# mcu_stm32h5.net
KiCad netlist of a schematic drawn in Altium Designer
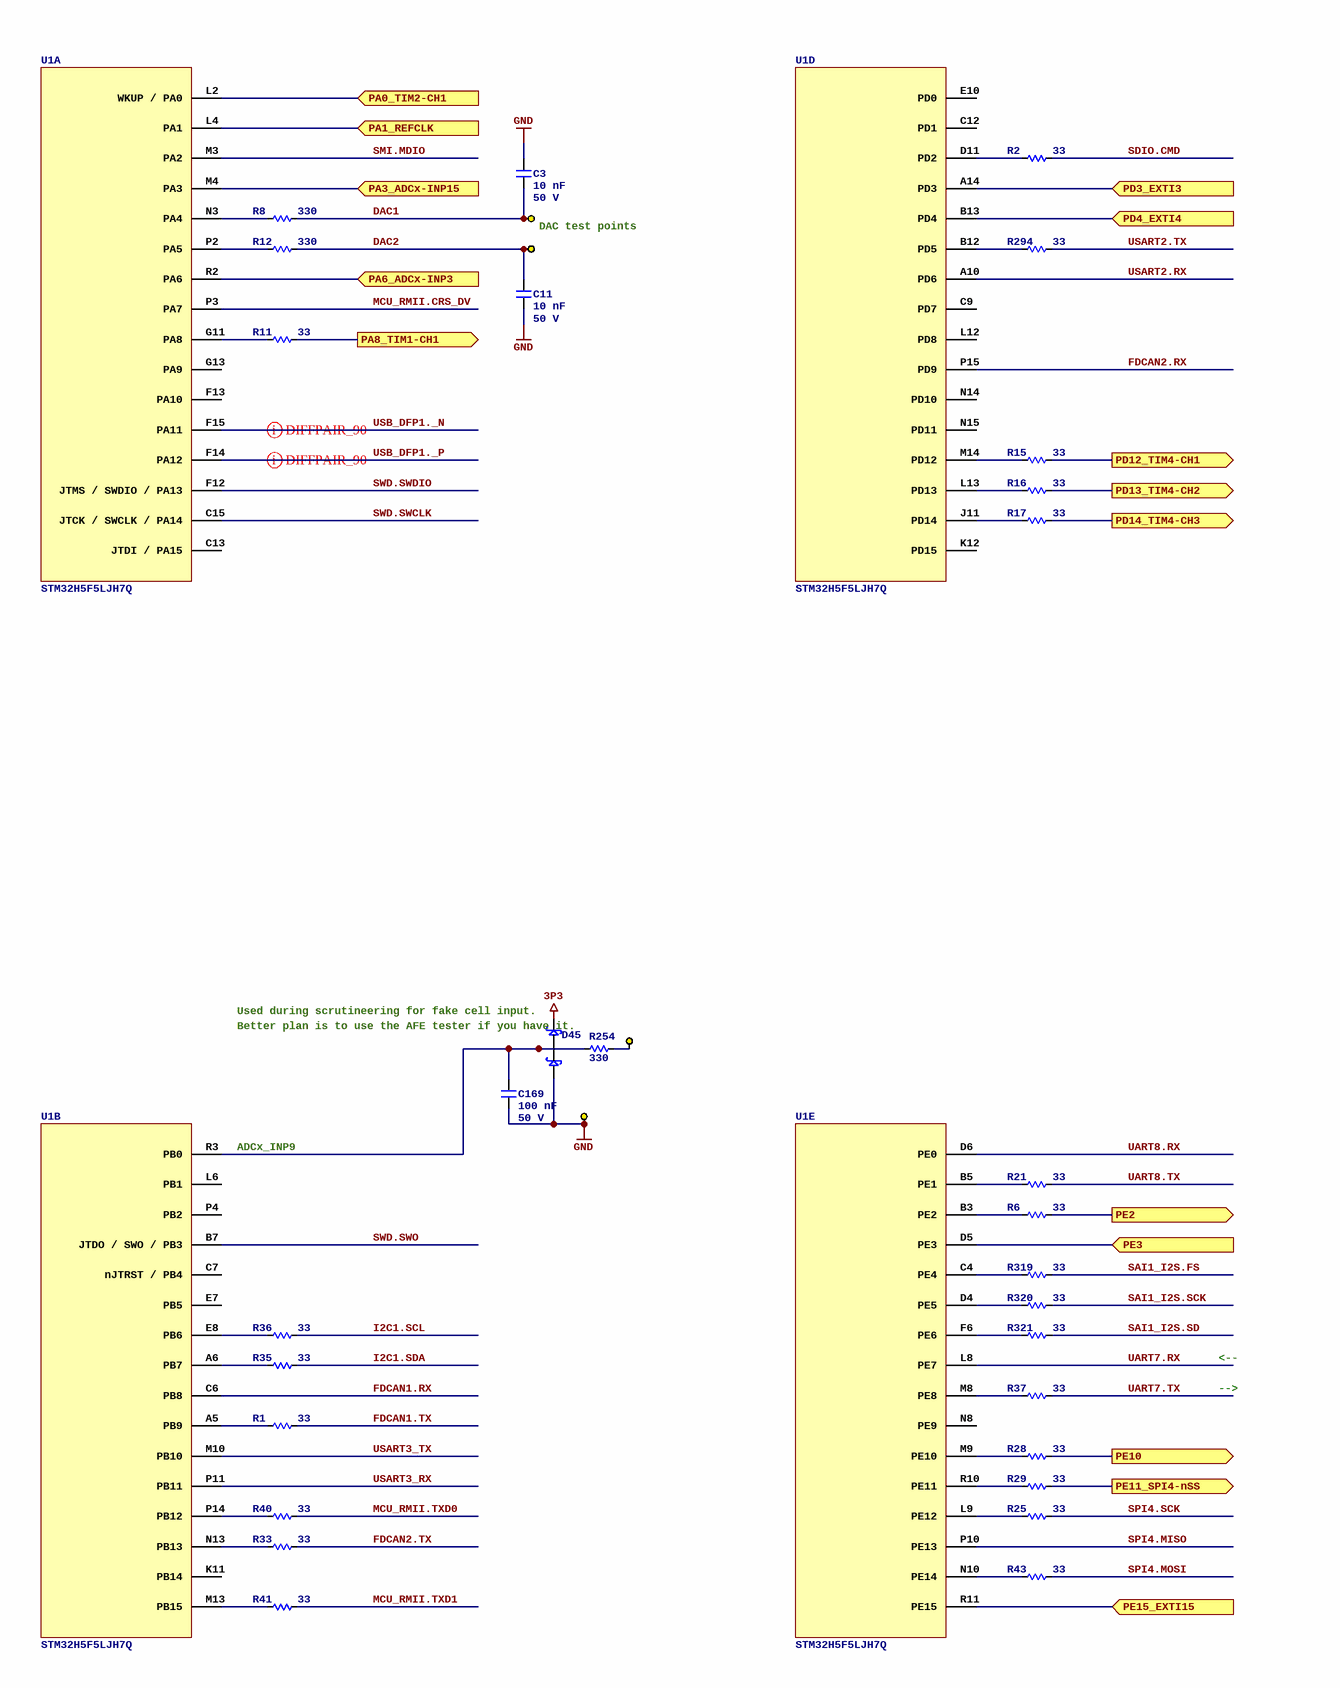
[diagram p0: mcu_stm32h5.SchDoc, top left]
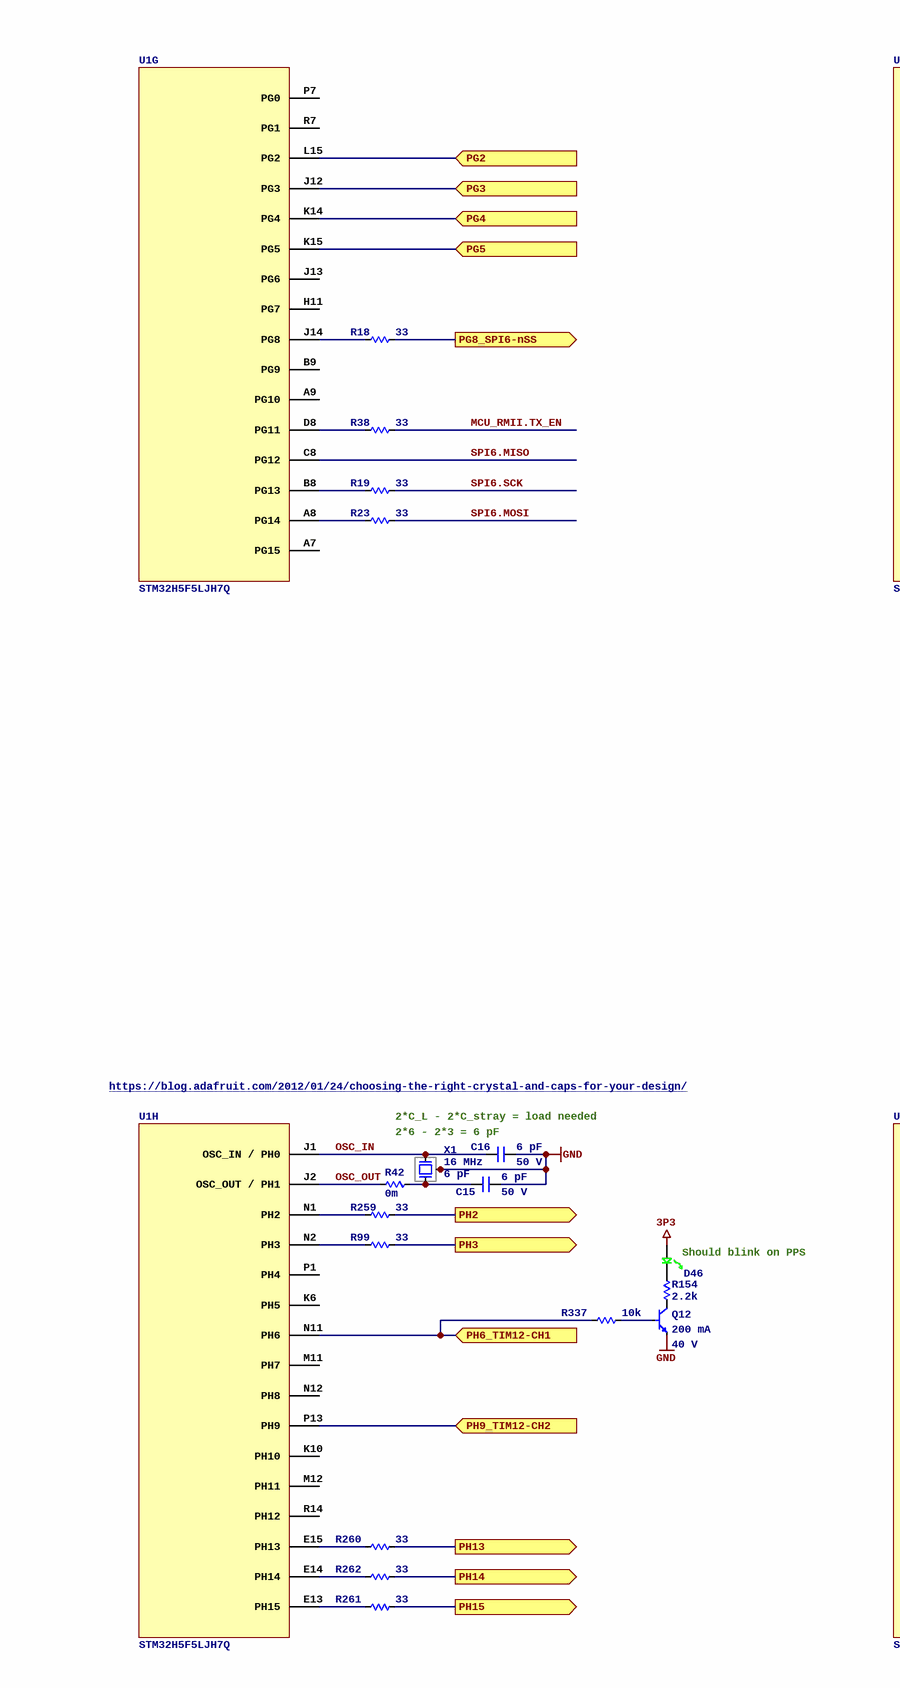
[diagram p1: mcu_stm32h5.SchDoc, top middle]
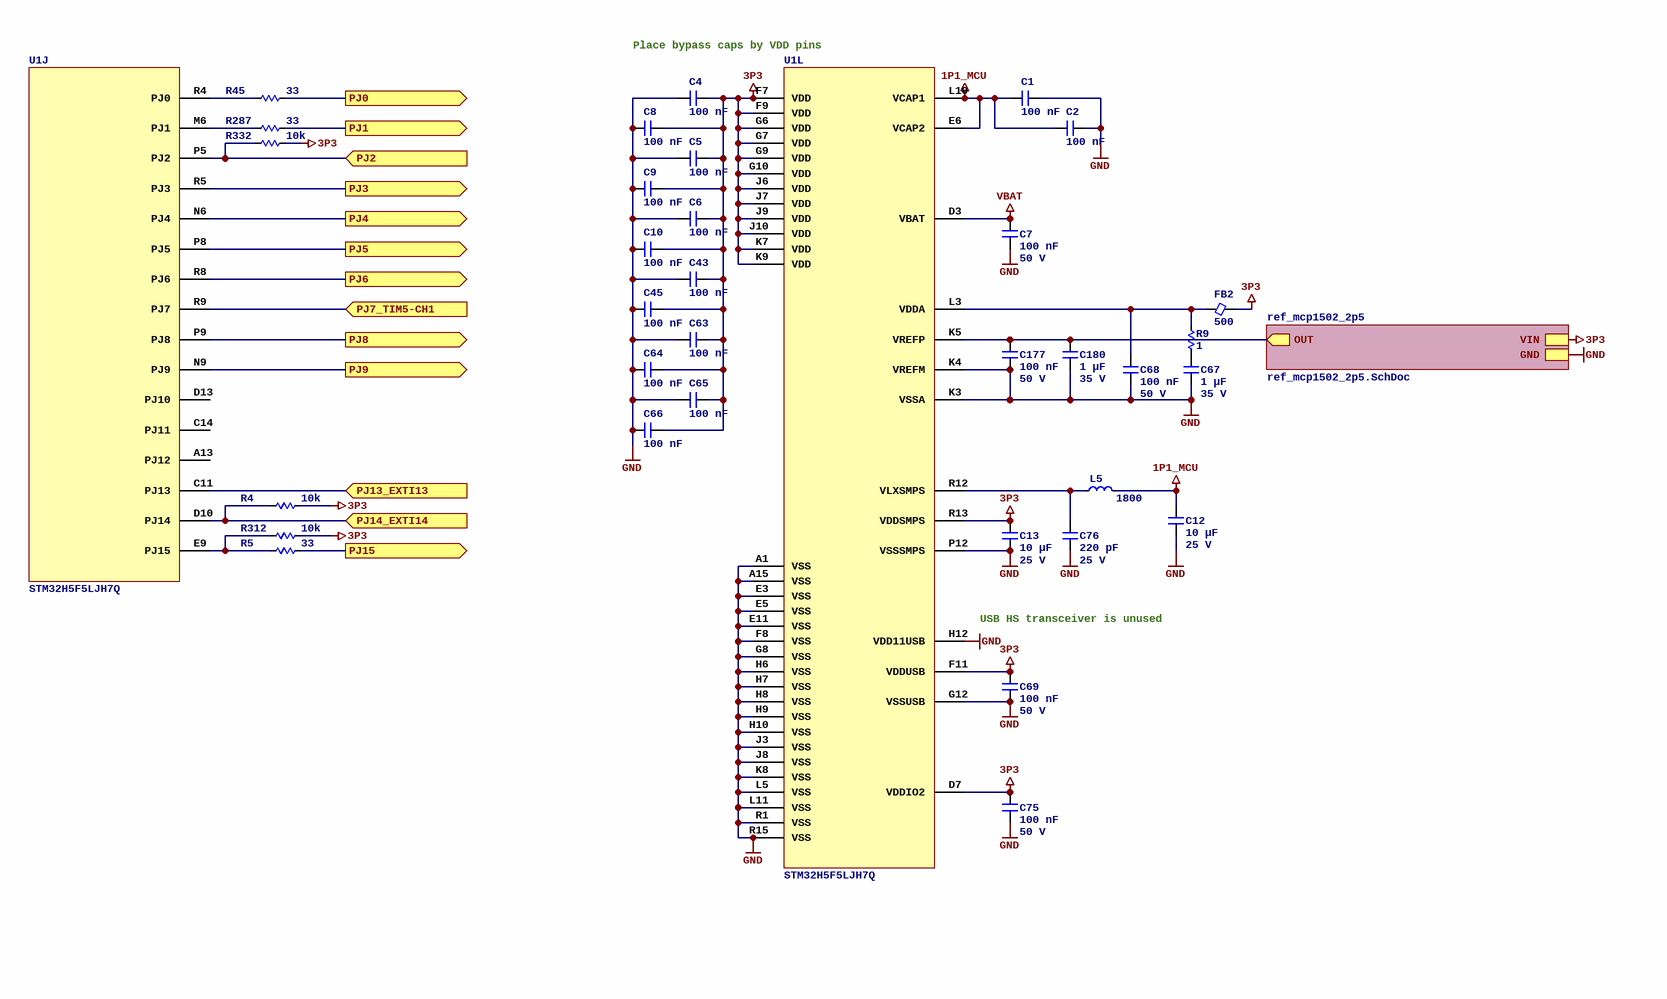
[diagram p2: mcu_stm32h5.SchDoc, top right]
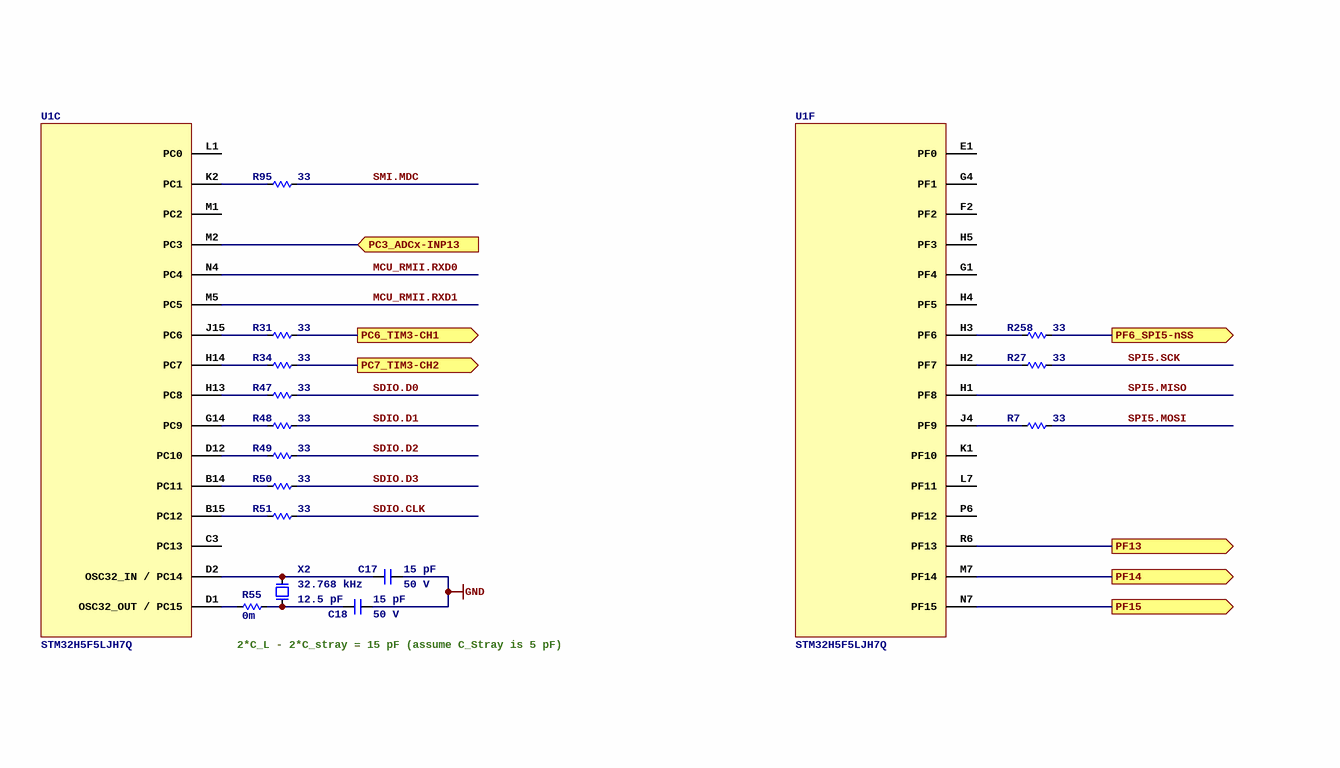
[diagram p3: mcu_stm32h5.SchDoc, bottom left]
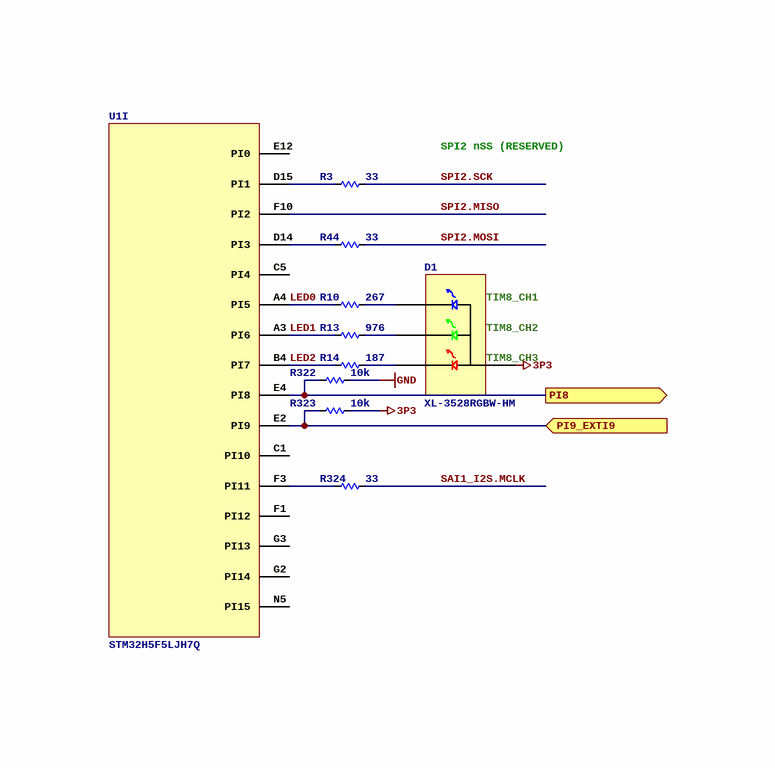
[diagram p4: mcu_stm32h5.SchDoc, bottom middle]
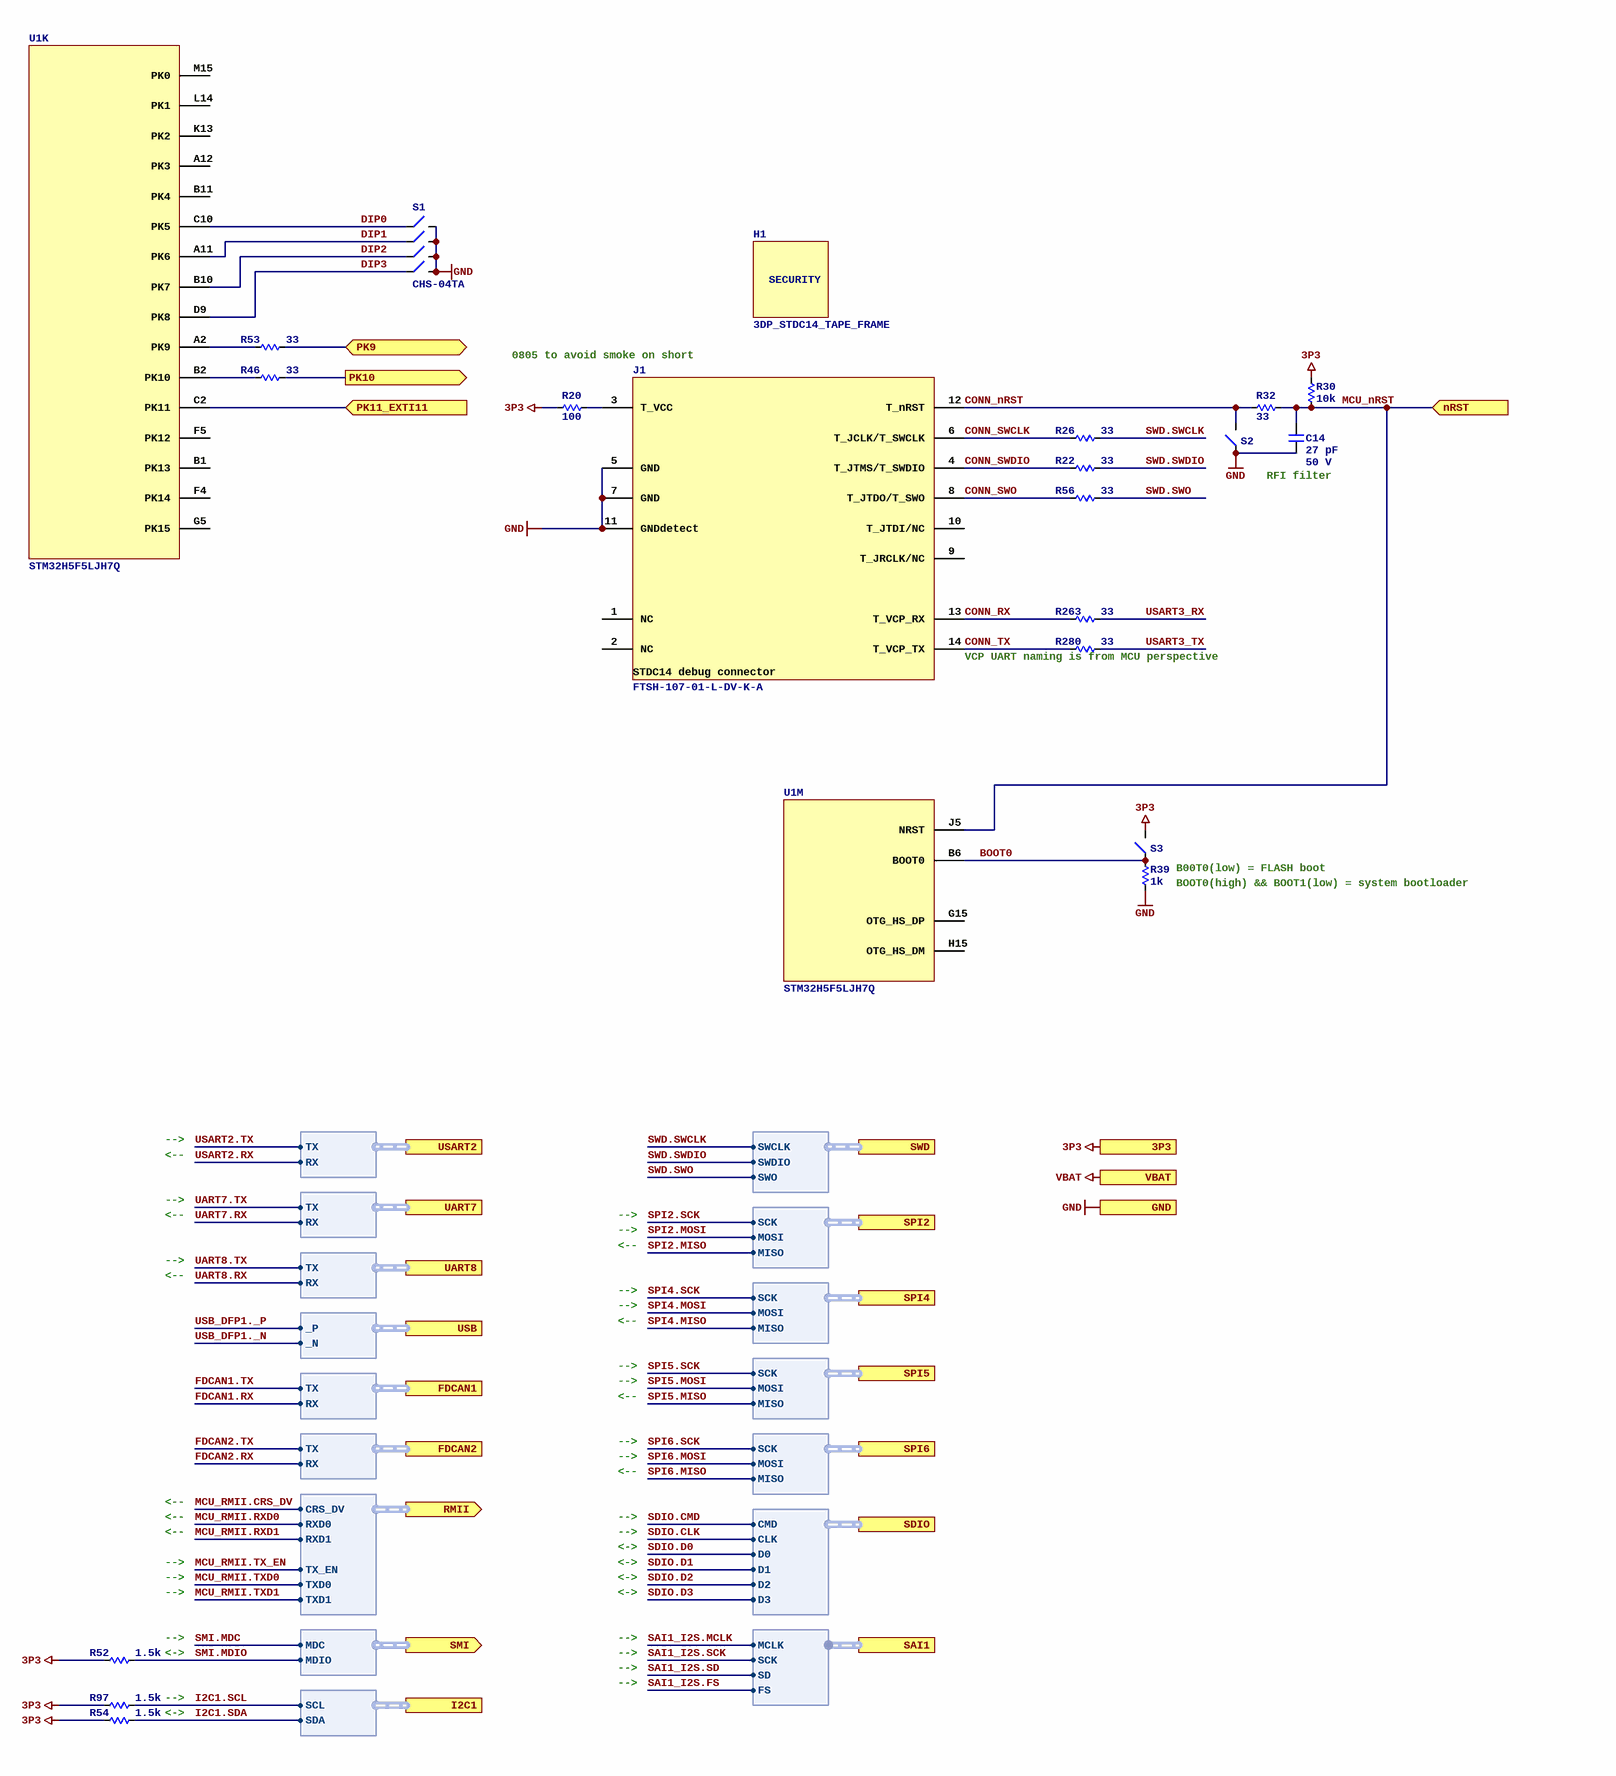
[diagram p5: mcu_stm32h5.SchDoc, bottom right]

(export (version "E")
  (design (tool "Eeschema 10.0.6"))
  (components
    (comp (ref "C1")
      (value "CL05B104KB54PNC")
      (footprint "C0402")
      (fields (field (name "CAPACITANCE") "100 nF") (field (name "MANUFACTURER") "Samsung Electro-Mechanics"))
      (libsource (lib "database") (part "__template_cap"))
    )
    (comp (ref "C2")
      (value "CL05B104KB54PNC")
      (footprint "C0402")
      (fields (field (name "CAPACITANCE") "100 nF") (field (name "MANUFACTURER") "Samsung Electro-Mechanics"))
      (libsource (lib "database") (part "__template_cap"))
    )
    (comp (ref "C3")
      (value "CL05B103KB5NNNC")
      (footprint "C0402")
      (fields
        (field (name "CAPACITANCE") "10 nF")
        (field (name "MANUFACTURER") "Samsung Electro-Mechanics")
        (field (name "VOLTAGE RATING") "50 V")
      )
      (libsource (lib "database") (part "__template_cap"))
    )
    (comp (ref "C4")
      (value "CL05B104KB54PNC")
      (footprint "C0402")
      (fields (field (name "CAPACITANCE") "100 nF") (field (name "MANUFACTURER") "Samsung Electro-Mechanics"))
      (libsource (lib "database") (part "__template_cap"))
    )
    (comp (ref "C5")
      (value "CL05B104KB54PNC")
      (footprint "C0402")
      (fields (field (name "CAPACITANCE") "100 nF") (field (name "MANUFACTURER") "Samsung Electro-Mechanics"))
      (libsource (lib "database") (part "__template_cap"))
    )
    (comp (ref "C6")
      (value "CL05B104KB54PNC")
      (footprint "C0402")
      (fields (field (name "CAPACITANCE") "100 nF") (field (name "MANUFACTURER") "Samsung Electro-Mechanics"))
      (libsource (lib "database") (part "__template_cap"))
    )
    (comp (ref "C7")
      (value "CL05B104KB54PNC")
      (footprint "C0402")
      (fields
        (field (name "CAPACITANCE") "100 nF")
        (field (name "MANUFACTURER") "Samsung Electro-Mechanics")
        (field (name "VOLTAGE RATING") "50 V")
      )
      (libsource (lib "database") (part "__template_cap"))
    )
    (comp (ref "C8")
      (value "CL05B104KB54PNC")
      (footprint "C0402")
      (fields (field (name "CAPACITANCE") "100 nF") (field (name "MANUFACTURER") "Samsung Electro-Mechanics"))
      (libsource (lib "database") (part "__template_cap"))
    )
    (comp (ref "C9")
      (value "CL05B104KB54PNC")
      (footprint "C0402")
      (fields (field (name "CAPACITANCE") "100 nF") (field (name "MANUFACTURER") "Samsung Electro-Mechanics"))
      (libsource (lib "database") (part "__template_cap"))
    )
    (comp (ref "C10")
      (value "CL05B104KB54PNC")
      (footprint "C0402")
      (fields (field (name "CAPACITANCE") "100 nF") (field (name "MANUFACTURER") "Samsung Electro-Mechanics"))
      (libsource (lib "database") (part "__template_cap"))
    )
    (comp (ref "C11")
      (value "CL05B103KB5NNNC")
      (footprint "C0402")
      (fields
        (field (name "CAPACITANCE") "10 nF")
        (field (name "MANUFACTURER") "Samsung Electro-Mechanics")
        (field (name "VOLTAGE RATING") "50 V")
      )
      (libsource (lib "database") (part "__template_cap"))
    )
    (comp (ref "C12")
      (value "CL10A106MA8NRNC")
      (footprint "C0603")
      (fields
        (field (name "CAPACITANCE") "10 µF")
        (field (name "MANUFACTURER") "Samsung Electro-Mechanics")
        (field (name "VOLTAGE RATING") "25 V")
      )
      (libsource (lib "database") (part "__template_cap"))
    )
    (comp (ref "C13")
      (value "CL10A106MA8NRNC")
      (footprint "C0603")
      (fields
        (field (name "CAPACITANCE") "10 µF")
        (field (name "MANUFACTURER") "Samsung Electro-Mechanics")
        (field (name "VOLTAGE RATING") "25 V")
      )
      (libsource (lib "database") (part "__template_cap"))
    )
    (comp (ref "C14")
      (value "0402CG270J500NT")
      (footprint "C0402")
      (fields
        (field (name "CAPACITANCE") "27 pF")
        (field (name "MANUFACTURER") "FH(Guangdong Fenghua Advanced Tech)")
        (field (name "VOLTAGE RATING") "50 V")
      )
      (libsource (lib "database") (part "__template_cap"))
    )
    (comp (ref "C15")
      (value "0402CG6R0C500NT")
      (footprint "C0402")
      (fields
        (field (name "CAPACITANCE") "6 pF")
        (field (name "MANUFACTURER") "FH(Guangdong Fenghua Advanced Tech)")
        (field (name "VOLTAGE RATING") "50 V")
      )
      (libsource (lib "database") (part "__template_cap"))
    )
    (comp (ref "C16")
      (value "0402CG6R0C500NT")
      (footprint "C0402")
      (fields
        (field (name "CAPACITANCE") "6 pF")
        (field (name "MANUFACTURER") "FH(Guangdong Fenghua Advanced Tech)")
        (field (name "VOLTAGE RATING") "50 V")
      )
      (libsource (lib "database") (part "__template_cap"))
    )
    (comp (ref "C17")
      (value "0402CG150J500NT")
      (footprint "C0402")
      (fields
        (field (name "CAPACITANCE") "15 pF")
        (field (name "MANUFACTURER") "FH(Guangdong Fenghua Advanced Tech)")
        (field (name "VOLTAGE RATING") "50 V")
      )
      (libsource (lib "database") (part "__template_cap"))
    )
    (comp (ref "C18")
      (value "0402CG150J500NT")
      (footprint "C0402")
      (fields
        (field (name "CAPACITANCE") "15 pF")
        (field (name "MANUFACTURER") "FH(Guangdong Fenghua Advanced Tech)")
        (field (name "VOLTAGE RATING") "50 V")
      )
      (libsource (lib "database") (part "__template_cap"))
    )
    (comp (ref "C43")
      (value "CL05B104KB54PNC")
      (footprint "C0402")
      (fields (field (name "CAPACITANCE") "100 nF") (field (name "MANUFACTURER") "Samsung Electro-Mechanics"))
      (libsource (lib "database") (part "__template_cap"))
    )
    (comp (ref "C45")
      (value "CL05B104KB54PNC")
      (footprint "C0402")
      (fields (field (name "CAPACITANCE") "100 nF") (field (name "MANUFACTURER") "Samsung Electro-Mechanics"))
      (libsource (lib "database") (part "__template_cap"))
    )
    (comp (ref "C63")
      (value "CL05B104KB54PNC")
      (footprint "C0402")
      (fields (field (name "CAPACITANCE") "100 nF") (field (name "MANUFACTURER") "Samsung Electro-Mechanics"))
      (libsource (lib "database") (part "__template_cap"))
    )
    (comp (ref "C64")
      (value "CL05B104KB54PNC")
      (footprint "C0402")
      (fields (field (name "CAPACITANCE") "100 nF") (field (name "MANUFACTURER") "Samsung Electro-Mechanics"))
      (libsource (lib "database") (part "__template_cap"))
    )
    (comp (ref "C65")
      (value "CL05B104KB54PNC")
      (footprint "C0402")
      (fields (field (name "CAPACITANCE") "100 nF") (field (name "MANUFACTURER") "Samsung Electro-Mechanics"))
      (libsource (lib "database") (part "__template_cap"))
    )
    (comp (ref "C66")
      (value "CL05B104KB54PNC")
      (footprint "C0402")
      (fields (field (name "CAPACITANCE") "100 nF") (field (name "MANUFACTURER") "Samsung Electro-Mechanics"))
      (libsource (lib "database") (part "__template_cap"))
    )
    (comp (ref "C67")
      (value "GMK107AB7105KAHT")
      (footprint "C0603")
      (fields
        (field (name "CAPACITANCE") "1 µF")
        (field (name "MANUFACTURER") "Taiyo Yuden")
        (field (name "VOLTAGE RATING") "35 V")
      )
      (libsource (lib "database") (part "__template_cap"))
    )
    (comp (ref "C68")
      (value "CL05B104KB54PNC")
      (footprint "C0402")
      (fields
        (field (name "CAPACITANCE") "100 nF")
        (field (name "MANUFACTURER") "Samsung Electro-Mechanics")
        (field (name "VOLTAGE RATING") "50 V")
      )
      (libsource (lib "database") (part "__template_cap"))
    )
    (comp (ref "C69")
      (value "CL05B104KB54PNC")
      (footprint "C0402")
      (fields
        (field (name "CAPACITANCE") "100 nF")
        (field (name "MANUFACTURER") "Samsung Electro-Mechanics")
        (field (name "VOLTAGE RATING") "50 V")
      )
      (libsource (lib "database") (part "__template_cap"))
    )
    (comp (ref "C75")
      (value "CL05B104KB54PNC")
      (footprint "C0402")
      (fields
        (field (name "CAPACITANCE") "100 nF")
        (field (name "MANUFACTURER") "Samsung Electro-Mechanics")
        (field (name "VOLTAGE RATING") "50 V")
      )
      (libsource (lib "database") (part "__template_cap"))
    )
    (comp (ref "C76")
      (value "04023A221JAT2A")
      (footprint "C0402")
      (fields
        (field (name "CAPACITANCE") "220 pF")
        (field (name "MANUFACTURER") "AVX")
        (field (name "VOLTAGE RATING") "25 V")
      )
      (libsource (lib "database") (part "__template_cap"))
    )
    (comp (ref "C169")
      (value "CL05B104KB54PNC")
      (footprint "C0402")
      (fields
        (field (name "CAPACITANCE") "100 nF")
        (field (name "MANUFACTURER") "Samsung Electro-Mechanics")
        (field (name "VOLTAGE RATING") "50 V")
      )
      (libsource (lib "database") (part "__template_cap"))
    )
    (comp (ref "C177")
      (value "CL05B104KB54PNC")
      (footprint "C0402")
      (fields
        (field (name "CAPACITANCE") "100 nF")
        (field (name "MANUFACTURER") "Samsung Electro-Mechanics")
        (field (name "VOLTAGE RATING") "50 V")
      )
      (libsource (lib "database") (part "__template_cap"))
    )
    (comp (ref "C180")
      (value "GMK107AB7105KAHT")
      (footprint "C0603")
      (fields
        (field (name "CAPACITANCE") "1 µF")
        (field (name "MANUFACTURER") "Taiyo Yuden")
        (field (name "VOLTAGE RATING") "35 V")
      )
      (libsource (lib "database") (part "__template_cap"))
    )
    (comp (ref "D1")
      (value "XL-3528RGBW-HM")
      (footprint "LED_RGB_SMD3528-4P")
      (description "LED Multi-Color Chip Red/Green/Blue 621nm/525nm/468nm 25mA/15mA/15mA 4-Pin PLCC T/R")
      (fields (field (name "MANUFACTURER") "XINGLIGHT"))
      (libsource (lib "database") (part "XL-3528RGBW-HM"))
    )
    (comp (ref "D45")
      (value "BAT54SLT1G")
      (footprint "3SOT23")
      (description "DIODE SCHOTTKY DUAL 30V SOT23")
      (fields (field (name "MANUFACTURER") "ON Semiconductor"))
      (libsource (lib "database") (part "BAT54SLT1G"))
    )
    (comp (ref "D46")
      (value "LTST-C190GKT")
      (footprint "LED_0603P_GREEN")
      (description "LED GREEN CLEAR 0603 SMD")
      (fields (field (name "MANUFACTURER") "Lite-On Inc"))
      (libsource (lib "database") (part "__template_led_green"))
    )
    (comp (ref "FB2")
      (value "BLM15AX601SN1D")
      (footprint "FB0402")
      (fields (field (name "MANUFACTURER") "Murata Electronics") (field (name "CURRENT RATING (MA)") "500"))
      (libsource (lib "database") (part "__template_fb"))
    )
    (comp (ref "H1")
      (value "3DP_STDC14_TAPE_FRAME")
      (footprint "3DP_STDC14_TAPE_FRAME")
      (description "3D-printed plastic frame used for security tape around STDC14 programming header")
      (fields (field (name "MANUFACTURER") "SSCP"))
      (libsource (lib "database") (part "3DP_STDC14_TAPE_FRAME"))
    )
    (comp (ref "J1")
      (value "FTSH-107-01-L-DV-K-A")
      (footprint "SAMTEC_FTSH-107-01-L-DV-K-A")
      (description "Connector Header Surface Mount 14 position 0.050\" (1.27mm)")
      (fields (field (name "MANUFACTURER") "Samtec"))
      (libsource (lib "database") (part "FTSH-107-01-L-DV-K-A"))
    )
    (comp (ref "L5")
      (value "DFE201612E-2R2M=P2")
      (footprint "MURATA_DFE201612E")
      (description "2.2 µH metal alloy power inductor")
      (fields (field (name "MANUFACTURER") "Murata Electronics") (field (name "CURRENT RATING (MA)") "1800"))
      (libsource (lib "database") (part "__template_inductor"))
    )
    (comp (ref "Q12")
      (value "MMBT3904T")
      (footprint "3SOT523")
      (description "Bipolar (BJT) Transistor NPN 40 V 200 mA 300MHz 150 mW Surface Mount SOT-523")
      (fields
        (field (name "MANUFACTURER") "Shenzhen Slkormicro Semicon Co., Ltd.")
        (field (name "CURRENT") "200 mA")
        (field (name "VOLTAGE") "40 V")
      )
      (libsource (lib "database") (part "MMBT3904T"))
    )
    (comp (ref "R1")
      (value "33")
      (footprint "R0402")
      (fields
        (field (name "TOLERANCE") "1%")
        (field (name "MANUFACTURER PART NUMBER") "0402WGF330JTCE")
        (field (name "MANUFACTURER") "UNI-ROYAL(Uniroyal Elec)")
      )
      (libsource (lib "database") (part "__template_resistor"))
    )
    (comp (ref "R2")
      (value "33")
      (footprint "R0402")
      (fields
        (field (name "TOLERANCE") "1%")
        (field (name "MANUFACTURER PART NUMBER") "0402WGF330JTCE")
        (field (name "MANUFACTURER") "UNI-ROYAL(Uniroyal Elec)")
      )
      (libsource (lib "database") (part "__template_resistor"))
    )
    (comp (ref "R3")
      (value "33")
      (footprint "R0402")
      (fields
        (field (name "TOLERANCE") "1%")
        (field (name "MANUFACTURER PART NUMBER") "0402WGF330JTCE")
        (field (name "MANUFACTURER") "UNI-ROYAL(Uniroyal Elec)")
      )
      (libsource (lib "database") (part "__template_resistor"))
    )
    (comp (ref "R4")
      (value "10k")
      (footprint "R0402")
      (fields
        (field (name "MANUFACTURER PART NUMBER") "0402WGF1002TCE")
        (field (name "MANUFACTURER") "UNI-ROYAL(Uniroyal Elec)")
        (field (name "TOLERANCE") "1%")
      )
      (libsource (lib "database") (part "__template_resistor"))
    )
    (comp (ref "R5")
      (value "33")
      (footprint "R0402")
      (fields
        (field (name "TOLERANCE") "1%")
        (field (name "MANUFACTURER PART NUMBER") "0402WGF330JTCE")
        (field (name "MANUFACTURER") "UNI-ROYAL(Uniroyal Elec)")
      )
      (libsource (lib "database") (part "__template_resistor"))
    )
    (comp (ref "R6")
      (value "33")
      (footprint "R0402")
      (fields
        (field (name "TOLERANCE") "1%")
        (field (name "MANUFACTURER PART NUMBER") "0402WGF330JTCE")
        (field (name "MANUFACTURER") "UNI-ROYAL(Uniroyal Elec)")
      )
      (libsource (lib "database") (part "__template_resistor"))
    )
    (comp (ref "R7")
      (value "33")
      (footprint "R0402")
      (fields
        (field (name "TOLERANCE") "1%")
        (field (name "MANUFACTURER PART NUMBER") "0402WGF330JTCE")
        (field (name "MANUFACTURER") "UNI-ROYAL(Uniroyal Elec)")
      )
      (libsource (lib "database") (part "__template_resistor"))
    )
    (comp (ref "R8")
      (value "330")
      (footprint "R0402")
      (fields
        (field (name "TOLERANCE") "1%")
        (field (name "MANUFACTURER PART NUMBER") "0402WGF3300TCE")
        (field (name "MANUFACTURER") "UNI-ROYAL(Uniroyal Elec)")
      )
      (libsource (lib "database") (part "__template_resistor"))
    )
    (comp (ref "R9")
      (value "1")
      (footprint "R0402")
      (fields
        (field (name "TOLERANCE") "1%")
        (field (name "MANUFACTURER PART NUMBER") "CRCW04021R00FKEDC")
        (field (name "MANUFACTURER") "Vishay Intertech")
      )
      (libsource (lib "database") (part "__template_resistor"))
    )
    (comp (ref "R10")
      (value "267")
      (footprint "R0402")
      (fields
        (field (name "TOLERANCE") "1%")
        (field (name "MANUFACTURER PART NUMBER") "FRC0402F2670TS")
        (field (name "MANUFACTURER") "FOJAN")
      )
      (libsource (lib "database") (part "__template_resistor"))
    )
    (comp (ref "R11")
      (value "33")
      (footprint "R0402")
      (fields
        (field (name "TOLERANCE") "1%")
        (field (name "MANUFACTURER PART NUMBER") "0402WGF330JTCE")
        (field (name "MANUFACTURER") "UNI-ROYAL(Uniroyal Elec)")
      )
      (libsource (lib "database") (part "__template_resistor"))
    )
    (comp (ref "R12")
      (value "330")
      (footprint "R0402")
      (fields
        (field (name "TOLERANCE") "1%")
        (field (name "MANUFACTURER PART NUMBER") "0402WGF3300TCE")
        (field (name "MANUFACTURER") "UNI-ROYAL(Uniroyal Elec)")
      )
      (libsource (lib "database") (part "__template_resistor"))
    )
    (comp (ref "R13")
      (value "976")
      (footprint "R0402")
      (fields
        (field (name "TOLERANCE") "1%")
        (field (name "MANUFACTURER PART NUMBER") "RTT029760FTH")
        (field (name "MANUFACTURER") "RALEC")
      )
      (libsource (lib "database") (part "__template_resistor"))
    )
    (comp (ref "R14")
      (value "187")
      (footprint "R0402")
      (fields
        (field (name "TOLERANCE") "1%")
        (field (name "MANUFACTURER PART NUMBER") "ERJ2RKF1870X")
        (field (name "MANUFACTURER") "PANASONIC")
      )
      (libsource (lib "database") (part "__template_resistor"))
    )
    (comp (ref "R15")
      (value "33")
      (footprint "R0402")
      (fields
        (field (name "TOLERANCE") "1%")
        (field (name "MANUFACTURER PART NUMBER") "0402WGF330JTCE")
        (field (name "MANUFACTURER") "UNI-ROYAL(Uniroyal Elec)")
      )
      (libsource (lib "database") (part "__template_resistor"))
    )
    (comp (ref "R16")
      (value "33")
      (footprint "R0402")
      (fields
        (field (name "TOLERANCE") "1%")
        (field (name "MANUFACTURER PART NUMBER") "0402WGF330JTCE")
        (field (name "MANUFACTURER") "UNI-ROYAL(Uniroyal Elec)")
      )
      (libsource (lib "database") (part "__template_resistor"))
    )
    (comp (ref "R17")
      (value "33")
      (footprint "R0402")
      (fields
        (field (name "TOLERANCE") "1%")
        (field (name "MANUFACTURER PART NUMBER") "0402WGF330JTCE")
        (field (name "MANUFACTURER") "UNI-ROYAL(Uniroyal Elec)")
      )
      (libsource (lib "database") (part "__template_resistor"))
    )
    (comp (ref "R18")
      (value "33")
      (footprint "R0402")
      (fields
        (field (name "TOLERANCE") "1%")
        (field (name "MANUFACTURER PART NUMBER") "0402WGF330JTCE")
        (field (name "MANUFACTURER") "UNI-ROYAL(Uniroyal Elec)")
      )
      (libsource (lib "database") (part "__template_resistor"))
    )
    (comp (ref "R19")
      (value "33")
      (footprint "R0402")
      (fields
        (field (name "TOLERANCE") "1%")
        (field (name "MANUFACTURER PART NUMBER") "0402WGF330JTCE")
        (field (name "MANUFACTURER") "UNI-ROYAL(Uniroyal Elec)")
      )
      (libsource (lib "database") (part "__template_resistor"))
    )
    (comp (ref "R20")
      (value "100")
      (footprint "R0805")
      (fields
        (field (name "TOLERANCE") "1%")
        (field (name "MANUFACTURER PART NUMBER") "ERJP06F1000V")
        (field (name "MANUFACTURER") "PANASONIC")
      )
      (libsource (lib "database") (part "__template_resistor"))
    )
    (comp (ref "R21")
      (value "33")
      (footprint "R0402")
      (fields
        (field (name "TOLERANCE") "1%")
        (field (name "MANUFACTURER PART NUMBER") "0402WGF330JTCE")
        (field (name "MANUFACTURER") "UNI-ROYAL(Uniroyal Elec)")
      )
      (libsource (lib "database") (part "__template_resistor"))
    )
    (comp (ref "R22")
      (value "33")
      (footprint "R0402")
      (fields
        (field (name "TOLERANCE") "1%")
        (field (name "MANUFACTURER PART NUMBER") "0402WGF330JTCE")
        (field (name "MANUFACTURER") "UNI-ROYAL(Uniroyal Elec)")
      )
      (libsource (lib "database") (part "__template_resistor"))
    )
    (comp (ref "R23")
      (value "33")
      (footprint "R0402")
      (fields
        (field (name "TOLERANCE") "1%")
        (field (name "MANUFACTURER PART NUMBER") "0402WGF330JTCE")
        (field (name "MANUFACTURER") "UNI-ROYAL(Uniroyal Elec)")
      )
      (libsource (lib "database") (part "__template_resistor"))
    )
    (comp (ref "R25")
      (value "33")
      (footprint "R0402")
      (fields
        (field (name "TOLERANCE") "1%")
        (field (name "MANUFACTURER PART NUMBER") "0402WGF330JTCE")
        (field (name "MANUFACTURER") "UNI-ROYAL(Uniroyal Elec)")
      )
      (libsource (lib "database") (part "__template_resistor"))
    )
    (comp (ref "R26")
      (value "33")
      (footprint "R0402")
      (fields
        (field (name "TOLERANCE") "1%")
        (field (name "MANUFACTURER PART NUMBER") "0402WGF330JTCE")
        (field (name "MANUFACTURER") "UNI-ROYAL(Uniroyal Elec)")
      )
      (libsource (lib "database") (part "__template_resistor"))
    )
    (comp (ref "R27")
      (value "33")
      (footprint "R0402")
      (fields
        (field (name "TOLERANCE") "1%")
        (field (name "MANUFACTURER PART NUMBER") "0402WGF330JTCE")
        (field (name "MANUFACTURER") "UNI-ROYAL(Uniroyal Elec)")
      )
      (libsource (lib "database") (part "__template_resistor"))
    )
    (comp (ref "R28")
      (value "33")
      (footprint "R0402")
      (fields
        (field (name "TOLERANCE") "1%")
        (field (name "MANUFACTURER PART NUMBER") "0402WGF330JTCE")
        (field (name "MANUFACTURER") "UNI-ROYAL(Uniroyal Elec)")
      )
      (libsource (lib "database") (part "__template_resistor"))
    )
    (comp (ref "R29")
      (value "33")
      (footprint "R0402")
      (fields
        (field (name "TOLERANCE") "1%")
        (field (name "MANUFACTURER PART NUMBER") "0402WGF330JTCE")
        (field (name "MANUFACTURER") "UNI-ROYAL(Uniroyal Elec)")
      )
      (libsource (lib "database") (part "__template_resistor"))
    )
    (comp (ref "R30")
      (value "10k")
      (footprint "R0402")
      (fields
        (field (name "TOLERANCE") "1%")
        (field (name "MANUFACTURER PART NUMBER") "0402WGF1002TCE")
        (field (name "MANUFACTURER") "UNI-ROYAL(Uniroyal Elec)")
      )
      (libsource (lib "database") (part "__template_resistor"))
    )
    (comp (ref "R31")
      (value "33")
      (footprint "R0402")
      (fields
        (field (name "TOLERANCE") "1%")
        (field (name "MANUFACTURER PART NUMBER") "0402WGF330JTCE")
        (field (name "MANUFACTURER") "UNI-ROYAL(Uniroyal Elec)")
      )
      (libsource (lib "database") (part "__template_resistor"))
    )
    (comp (ref "R32")
      (value "33")
      (footprint "R0402")
      (fields
        (field (name "TOLERANCE") "1%")
        (field (name "MANUFACTURER PART NUMBER") "0402WGF330JTCE")
        (field (name "MANUFACTURER") "UNI-ROYAL(Uniroyal Elec)")
      )
      (libsource (lib "database") (part "__template_resistor"))
    )
    (comp (ref "R33")
      (value "33")
      (footprint "R0402")
      (fields
        (field (name "TOLERANCE") "1%")
        (field (name "MANUFACTURER PART NUMBER") "0402WGF330JTCE")
        (field (name "MANUFACTURER") "UNI-ROYAL(Uniroyal Elec)")
      )
      (libsource (lib "database") (part "__template_resistor"))
    )
    (comp (ref "R34")
      (value "33")
      (footprint "R0402")
      (fields
        (field (name "TOLERANCE") "1%")
        (field (name "MANUFACTURER PART NUMBER") "0402WGF330JTCE")
        (field (name "MANUFACTURER") "UNI-ROYAL(Uniroyal Elec)")
      )
      (libsource (lib "database") (part "__template_resistor"))
    )
    (comp (ref "R35")
      (value "33")
      (footprint "R0402")
      (fields
        (field (name "TOLERANCE") "1%")
        (field (name "MANUFACTURER PART NUMBER") "0402WGF330JTCE")
        (field (name "MANUFACTURER") "UNI-ROYAL(Uniroyal Elec)")
      )
      (libsource (lib "database") (part "__template_resistor"))
    )
    (comp (ref "R36")
      (value "33")
      (footprint "R0402")
      (fields
        (field (name "TOLERANCE") "1%")
        (field (name "MANUFACTURER PART NUMBER") "0402WGF330JTCE")
        (field (name "MANUFACTURER") "UNI-ROYAL(Uniroyal Elec)")
      )
      (libsource (lib "database") (part "__template_resistor"))
    )
    (comp (ref "R37")
      (value "33")
      (footprint "R0402")
      (fields
        (field (name "TOLERANCE") "1%")
        (field (name "MANUFACTURER PART NUMBER") "0402WGF330JTCE")
        (field (name "MANUFACTURER") "UNI-ROYAL(Uniroyal Elec)")
      )
      (libsource (lib "database") (part "__template_resistor"))
    )
    (comp (ref "R38")
      (value "33")
      (footprint "R0402")
      (fields
        (field (name "TOLERANCE") "1%")
        (field (name "MANUFACTURER PART NUMBER") "0402WGF330JTCE")
        (field (name "MANUFACTURER") "UNI-ROYAL(Uniroyal Elec)")
      )
      (libsource (lib "database") (part "__template_resistor"))
    )
    (comp (ref "R39")
      (value "1k")
      (footprint "R0402")
      (fields
        (field (name "TOLERANCE") "1%")
        (field (name "MANUFACTURER PART NUMBER") "0402WGF1001TCE")
        (field (name "MANUFACTURER") "UNI-ROYAL(Uniroyal Elec)")
      )
      (libsource (lib "database") (part "__template_resistor"))
    )
    (comp (ref "R40")
      (value "33")
      (footprint "R0402")
      (fields
        (field (name "TOLERANCE") "1%")
        (field (name "MANUFACTURER PART NUMBER") "0402WGF330JTCE")
        (field (name "MANUFACTURER") "UNI-ROYAL(Uniroyal Elec)")
      )
      (libsource (lib "database") (part "__template_resistor"))
    )
    (comp (ref "R41")
      (value "33")
      (footprint "R0402")
      (fields
        (field (name "TOLERANCE") "1%")
        (field (name "MANUFACTURER PART NUMBER") "0402WGF330JTCE")
        (field (name "MANUFACTURER") "UNI-ROYAL(Uniroyal Elec)")
      )
      (libsource (lib "database") (part "__template_resistor"))
    )
    (comp (ref "R42")
      (value "0m")
      (footprint "R0402")
      (fields
        (field (name "MANUFACTURER PART NUMBER") "0402WGF0000TCE")
        (field (name "MANUFACTURER") "UNI-ROYAL(Uniroyal Elec)")
      )
      (libsource (lib "database") (part "__template_resistor"))
    )
    (comp (ref "R43")
      (value "33")
      (footprint "R0402")
      (fields
        (field (name "TOLERANCE") "1%")
        (field (name "MANUFACTURER PART NUMBER") "0402WGF330JTCE")
        (field (name "MANUFACTURER") "UNI-ROYAL(Uniroyal Elec)")
      )
      (libsource (lib "database") (part "__template_resistor"))
    )
    (comp (ref "R44")
      (value "33")
      (footprint "R0402")
      (fields
        (field (name "TOLERANCE") "1%")
        (field (name "MANUFACTURER PART NUMBER") "0402WGF330JTCE")
        (field (name "MANUFACTURER") "UNI-ROYAL(Uniroyal Elec)")
      )
      (libsource (lib "database") (part "__template_resistor"))
    )
    (comp (ref "R45")
      (value "33")
      (footprint "R0402")
      (fields
        (field (name "TOLERANCE") "1%")
        (field (name "MANUFACTURER PART NUMBER") "0402WGF330JTCE")
        (field (name "MANUFACTURER") "UNI-ROYAL(Uniroyal Elec)")
      )
      (libsource (lib "database") (part "__template_resistor"))
    )
    (comp (ref "R46")
      (value "33")
      (footprint "R0402")
      (fields
        (field (name "TOLERANCE") "1%")
        (field (name "MANUFACTURER PART NUMBER") "0402WGF330JTCE")
        (field (name "MANUFACTURER") "UNI-ROYAL(Uniroyal Elec)")
      )
      (libsource (lib "database") (part "__template_resistor"))
    )
    (comp (ref "R47")
      (value "33")
      (footprint "R0402")
      (fields
        (field (name "TOLERANCE") "1%")
        (field (name "MANUFACTURER PART NUMBER") "0402WGF330JTCE")
        (field (name "MANUFACTURER") "UNI-ROYAL(Uniroyal Elec)")
      )
      (libsource (lib "database") (part "__template_resistor"))
    )
    (comp (ref "R48")
      (value "33")
      (footprint "R0402")
      (fields
        (field (name "TOLERANCE") "1%")
        (field (name "MANUFACTURER PART NUMBER") "0402WGF330JTCE")
        (field (name "MANUFACTURER") "UNI-ROYAL(Uniroyal Elec)")
      )
      (libsource (lib "database") (part "__template_resistor"))
    )
    (comp (ref "R49")
      (value "33")
      (footprint "R0402")
      (fields
        (field (name "TOLERANCE") "1%")
        (field (name "MANUFACTURER PART NUMBER") "0402WGF330JTCE")
        (field (name "MANUFACTURER") "UNI-ROYAL(Uniroyal Elec)")
      )
      (libsource (lib "database") (part "__template_resistor"))
    )
    (comp (ref "R50")
      (value "33")
      (footprint "R0402")
      (fields
        (field (name "TOLERANCE") "1%")
        (field (name "MANUFACTURER PART NUMBER") "0402WGF330JTCE")
        (field (name "MANUFACTURER") "UNI-ROYAL(Uniroyal Elec)")
      )
      (libsource (lib "database") (part "__template_resistor"))
    )
    (comp (ref "R51")
      (value "33")
      (footprint "R0402")
      (fields
        (field (name "TOLERANCE") "1%")
        (field (name "MANUFACTURER PART NUMBER") "0402WGF330JTCE")
        (field (name "MANUFACTURER") "UNI-ROYAL(Uniroyal Elec)")
      )
      (libsource (lib "database") (part "__template_resistor"))
    )
    (comp (ref "R52")
      (value "1.5k")
      (footprint "R0402")
      (fields
        (field (name "TOLERANCE") "1%")
        (field (name "MANUFACTURER PART NUMBER") "0402WGF1501TCE")
        (field (name "MANUFACTURER") "UNI-ROYAL(Uniroyal Elec)")
      )
      (libsource (lib "database") (part "__template_resistor"))
    )
    (comp (ref "R53")
      (value "33")
      (footprint "R0402")
      (fields
        (field (name "TOLERANCE") "1%")
        (field (name "MANUFACTURER PART NUMBER") "0402WGF330JTCE")
        (field (name "MANUFACTURER") "UNI-ROYAL(Uniroyal Elec)")
      )
      (libsource (lib "database") (part "__template_resistor"))
    )
    (comp (ref "R54")
      (value "1.5k")
      (footprint "R0402")
      (fields
        (field (name "TOLERANCE") "1%")
        (field (name "MANUFACTURER PART NUMBER") "0402WGF1501TCE")
        (field (name "MANUFACTURER") "UNI-ROYAL(Uniroyal Elec)")
      )
      (libsource (lib "database") (part "__template_resistor"))
    )
    (comp (ref "R55")
      (value "0m")
      (footprint "R0402")
      (fields
        (field (name "MANUFACTURER PART NUMBER") "0402WGF0000TCE")
        (field (name "MANUFACTURER") "UNI-ROYAL(Uniroyal Elec)")
      )
      (libsource (lib "database") (part "__template_resistor"))
    )
    (comp (ref "R56")
      (value "33")
      (footprint "R0402")
      (fields
        (field (name "TOLERANCE") "1%")
        (field (name "MANUFACTURER PART NUMBER") "0402WGF330JTCE")
        (field (name "MANUFACTURER") "UNI-ROYAL(Uniroyal Elec)")
      )
      (libsource (lib "database") (part "__template_resistor"))
    )
    (comp (ref "R95")
      (value "33")
      (footprint "R0402")
      (fields
        (field (name "TOLERANCE") "1%")
        (field (name "MANUFACTURER PART NUMBER") "0402WGF330JTCE")
        (field (name "MANUFACTURER") "UNI-ROYAL(Uniroyal Elec)")
      )
      (libsource (lib "database") (part "__template_resistor"))
    )
    (comp (ref "R97")
      (value "1.5k")
      (footprint "R0402")
      (fields
        (field (name "TOLERANCE") "1%")
        (field (name "MANUFACTURER PART NUMBER") "0402WGF1501TCE")
        (field (name "MANUFACTURER") "UNI-ROYAL(Uniroyal Elec)")
      )
      (libsource (lib "database") (part "__template_resistor"))
    )
    (comp (ref "R99")
      (value "33")
      (footprint "R0402")
      (fields
        (field (name "TOLERANCE") "1%")
        (field (name "MANUFACTURER PART NUMBER") "0402WGF330JTCE")
        (field (name "MANUFACTURER") "UNI-ROYAL(Uniroyal Elec)")
      )
      (libsource (lib "database") (part "__template_resistor"))
    )
    (comp (ref "R154")
      (value "2.2k")
      (footprint "R0402")
      (fields
        (field (name "TOLERANCE") "1%")
        (field (name "MANUFACTURER PART NUMBER") "0402WGF2201TCE")
        (field (name "MANUFACTURER") "UNI-ROYAL(Uniroyal Elec)")
      )
      (libsource (lib "database") (part "__template_resistor"))
    )
    (comp (ref "R254")
      (value "330")
      (footprint "R0402")
      (fields
        (field (name "TOLERANCE") "1%")
        (field (name "MANUFACTURER PART NUMBER") "0402WGF3300TCE")
        (field (name "MANUFACTURER") "UNI-ROYAL(Uniroyal Elec)")
      )
      (libsource (lib "database") (part "__template_resistor"))
    )
    (comp (ref "R258")
      (value "33")
      (footprint "R0402")
      (fields
        (field (name "TOLERANCE") "1%")
        (field (name "MANUFACTURER PART NUMBER") "0402WGF330JTCE")
        (field (name "MANUFACTURER") "UNI-ROYAL(Uniroyal Elec)")
      )
      (libsource (lib "database") (part "__template_resistor"))
    )
    (comp (ref "R259")
      (value "33")
      (footprint "R0402")
      (fields
        (field (name "TOLERANCE") "1%")
        (field (name "MANUFACTURER PART NUMBER") "0402WGF330JTCE")
        (field (name "MANUFACTURER") "UNI-ROYAL(Uniroyal Elec)")
      )
      (libsource (lib "database") (part "__template_resistor"))
    )
    (comp (ref "R260")
      (value "33")
      (footprint "R0402")
      (fields
        (field (name "TOLERANCE") "1%")
        (field (name "MANUFACTURER PART NUMBER") "0402WGF330JTCE")
        (field (name "MANUFACTURER") "UNI-ROYAL(Uniroyal Elec)")
      )
      (libsource (lib "database") (part "__template_resistor"))
    )
    (comp (ref "R261")
      (value "33")
      (footprint "R0402")
      (fields
        (field (name "TOLERANCE") "1%")
        (field (name "MANUFACTURER PART NUMBER") "0402WGF330JTCE")
        (field (name "MANUFACTURER") "UNI-ROYAL(Uniroyal Elec)")
      )
      (libsource (lib "database") (part "__template_resistor"))
    )
    (comp (ref "R262")
      (value "33")
      (footprint "R0402")
      (fields
        (field (name "TOLERANCE") "1%")
        (field (name "MANUFACTURER PART NUMBER") "0402WGF330JTCE")
        (field (name "MANUFACTURER") "UNI-ROYAL(Uniroyal Elec)")
      )
      (libsource (lib "database") (part "__template_resistor"))
    )
    (comp (ref "R263")
      (value "33")
      (footprint "R0402")
      (fields
        (field (name "TOLERANCE") "1%")
        (field (name "MANUFACTURER PART NUMBER") "0402WGF330JTCE")
        (field (name "MANUFACTURER") "UNI-ROYAL(Uniroyal Elec)")
      )
      (libsource (lib "database") (part "__template_resistor"))
    )
    (comp (ref "R280")
      (value "33")
      (footprint "R0402")
      (fields
        (field (name "TOLERANCE") "1%")
        (field (name "MANUFACTURER PART NUMBER") "0402WGF330JTCE")
        (field (name "MANUFACTURER") "UNI-ROYAL(Uniroyal Elec)")
      )
      (libsource (lib "database") (part "__template_resistor"))
    )
    (comp (ref "R287")
      (value "33")
      (footprint "R0402")
      (fields
        (field (name "TOLERANCE") "1%")
        (field (name "MANUFACTURER PART NUMBER") "0402WGF330JTCE")
        (field (name "MANUFACTURER") "UNI-ROYAL(Uniroyal Elec)")
      )
      (libsource (lib "database") (part "__template_resistor"))
    )
    (comp (ref "R294")
      (value "33")
      (footprint "R0402")
      (fields
        (field (name "TOLERANCE") "1%")
        (field (name "MANUFACTURER PART NUMBER") "0402WGF330JTCE")
        (field (name "MANUFACTURER") "UNI-ROYAL(Uniroyal Elec)")
      )
      (libsource (lib "database") (part "__template_resistor"))
    )
    (comp (ref "R312")
      (value "10k")
      (footprint "R0402")
      (fields
        (field (name "MANUFACTURER PART NUMBER") "0402WGF1002TCE")
        (field (name "MANUFACTURER") "UNI-ROYAL(Uniroyal Elec)")
        (field (name "TOLERANCE") "1%")
      )
      (libsource (lib "database") (part "__template_resistor"))
    )
    (comp (ref "R319")
      (value "33")
      (footprint "R0402")
      (fields
        (field (name "TOLERANCE") "1%")
        (field (name "MANUFACTURER PART NUMBER") "0402WGF330JTCE")
        (field (name "MANUFACTURER") "UNI-ROYAL(Uniroyal Elec)")
      )
      (libsource (lib "database") (part "__template_resistor"))
    )
    (comp (ref "R320")
      (value "33")
      (footprint "R0402")
      (fields
        (field (name "TOLERANCE") "1%")
        (field (name "MANUFACTURER PART NUMBER") "0402WGF330JTCE")
        (field (name "MANUFACTURER") "UNI-ROYAL(Uniroyal Elec)")
      )
      (libsource (lib "database") (part "__template_resistor"))
    )
    (comp (ref "R321")
      (value "33")
      (footprint "R0402")
      (fields
        (field (name "TOLERANCE") "1%")
        (field (name "MANUFACTURER PART NUMBER") "0402WGF330JTCE")
        (field (name "MANUFACTURER") "UNI-ROYAL(Uniroyal Elec)")
      )
      (libsource (lib "database") (part "__template_resistor"))
    )
    (comp (ref "R322")
      (value "10k")
      (footprint "R0402")
      (fields
        (field (name "MANUFACTURER PART NUMBER") "0402WGF1002TCE")
        (field (name "MANUFACTURER") "UNI-ROYAL(Uniroyal Elec)")
        (field (name "TOLERANCE") "1%")
      )
      (libsource (lib "database") (part "__template_resistor"))
    )
    (comp (ref "R323")
      (value "10k")
      (footprint "R0402")
      (fields
        (field (name "MANUFACTURER PART NUMBER") "0402WGF1002TCE")
        (field (name "MANUFACTURER") "UNI-ROYAL(Uniroyal Elec)")
        (field (name "TOLERANCE") "1%")
      )
      (libsource (lib "database") (part "__template_resistor"))
    )
    (comp (ref "R324")
      (value "33")
      (footprint "R0402")
      (fields
        (field (name "TOLERANCE") "1%")
        (field (name "MANUFACTURER PART NUMBER") "0402WGF330JTCE")
        (field (name "MANUFACTURER") "UNI-ROYAL(Uniroyal Elec)")
      )
      (libsource (lib "database") (part "__template_resistor"))
    )
    (comp (ref "R332")
      (value "10k")
      (footprint "R0402")
      (fields
        (field (name "TOLERANCE") "1%")
        (field (name "MANUFACTURER PART NUMBER") "0402WGF1002TCE")
        (field (name "MANUFACTURER") "UNI-ROYAL(Uniroyal Elec)")
      )
      (libsource (lib "database") (part "__template_resistor"))
    )
    (comp (ref "R337")
      (value "10k")
      (footprint "R0402")
      (fields
        (field (name "MANUFACTURER PART NUMBER") "0402WGF1002TCE")
        (field (name "MANUFACTURER") "UNI-ROYAL(Uniroyal Elec)")
        (field (name "TOLERANCE") "1%")
      )
      (libsource (lib "database") (part "__template_resistor"))
    )
    (comp (ref "S1")
      (value "CHS-04TA")
      (footprint "SWITCH_NIDEC_CHS-04TA")
      (description "DIP Switch, Slide, SPST, Flush, Recessed, 6VDC, 100mA, CHS Series Ž Nidec Components CHS-04TA")
      (fields (field (name "MANUFACTURER") "Nidec Copal"))
      (libsource (lib "database") (part "CHS-04TA"))
    )
    (comp (ref "S2")
      (value "TS-1092S-B3D2-G")
      (footprint "SWITCH_TS-1092S-B3D2-G")
      (description "SWITCH TACTILE SPST-NO")
      (fields (field (name "MANUFACTURER") "Yuandi"))
      (libsource (lib "database") (part "TS-1092S-B3D2-G"))
    )
    (comp (ref "S3")
      (value "TS-1092S-B3D2-G")
      (footprint "SWITCH_TS-1092S-B3D2-G")
      (description "SWITCH TACTILE SPST-NO")
      (fields (field (name "MANUFACTURER") "Yuandi"))
      (libsource (lib "database") (part "TS-1092S-B3D2-G"))
    )
    (comp (ref "TP1")
      (value "RH-5002")
      (footprint "TP_RH-5002")
      (description "White through-hole PCB test point")
      (fields (field (name "MANUFACTURER") "ronghe"))
      (libsource (lib "database") (part "__template_testpoint"))
    )
    (comp (ref "TP2")
      (value "RH-5002")
      (footprint "TP_RH-5002")
      (description "White through-hole PCB test point")
      (fields (field (name "MANUFACTURER") "ronghe"))
      (libsource (lib "database") (part "__template_testpoint"))
    )
    (comp (ref "TP51")
      (value "RH-5000")
      (footprint "TP_RH-5000")
      (description "Red through-hole PCB test point")
      (fields (field (name "MANUFACTURER") "ronghe"))
      (libsource (lib "database") (part "__template_testpoint"))
    )
    (comp (ref "TP52")
      (value "RH-5001")
      (footprint "TP_RH-5001")
      (description "Black through-hole PCB test point")
      (fields (field (name "MANUFACTURER") "ronghe"))
      (libsource (lib "database") (part "__template_testpoint"))
    )
    (comp (ref "U1")
      (value "STM32H5F5LJH7Q")
      (footprint "ST_TFBGA225")
      (description "ARM® Cortex®-M33F STM32H5 Microcontroller IC 32-Bit 250MHz 4MB (4M x 8) FLASH 225-TFBGA (13x13)")
      (fields (field (name "MANUFACTURER") "STMicroelectronics"))
      (libsource (lib "database") (part "STM32H5F5LJH7Q"))
    )
    (comp (ref "X1")
      (value "XRCGB16M000FXN00R0")
      (footprint "4_SMD_2.0X1.6MM")
      (description "CRYSTAL 16.0000MHZ 6PF SMD")
      (fields
        (field (name "MANUFACTURER") "Murata")
        (field (name "FREQUENCY") "16 MHz")
        (field (name "CAPACITANCE") "6 pF")
      )
      (libsource (lib "database") (part "__template_crystal_4pin"))
    )
    (comp (ref "X2")
      (value "9HT10-32.768KEZF-T")
      (footprint "XTAL_TXC_9HT10")
      (description "CRYSTAL 32.768 KHZ 12.5 PF SMD")
      (fields
        (field (name "MANUFACTURER") "TXC CORPORATION")
        (field (name "FREQUENCY") "32.768 kHz")
        (field (name "CAPACITANCE") "12.5 pF")
      )
      (libsource (lib "database") (part "__template_crystal_2pin"))
    )
  )
  (nets
    (net (code "11") (name "/BOOT0") (class "Default")
      (node (ref "R39") (pin "1") (pintype "passive"))
      (node (ref "S3") (pin "1") (pintype "passive"))
      (node (ref "U1") (pin "B6") (pinfunction "BOOT0_B6") (pintype "passive"))
    )
    (net (code "12") (name "/CONN_RX") (class "Default")
      (node (ref "J1") (pin "13") (pinfunction "T_VCP_RX_13") (pintype "passive"))
      (node (ref "R263") (pin "2") (pintype "passive"))
    )
    (net (code "13") (name "/CONN_SWCLK") (class "Default")
      (node (ref "J1") (pin "6") (pinfunction "T_JCLK/T_SWCLK_6") (pintype "passive"))
      (node (ref "R26") (pin "2") (pintype "passive"))
    )
    (net (code "14") (name "/CONN_SWDIO") (class "Default")
      (node (ref "J1") (pin "4") (pinfunction "T_JTMS/T_SWDIO_4") (pintype "passive"))
      (node (ref "R22") (pin "2") (pintype "passive"))
    )
    (net (code "15") (name "/CONN_SWO") (class "Default")
      (node (ref "J1") (pin "8") (pinfunction "T_JTDO/T_SWO_8") (pintype "passive"))
      (node (ref "R56") (pin "2") (pintype "passive"))
    )
    (net (code "16") (name "/CONN_TX") (class "Default")
      (node (ref "J1") (pin "14") (pinfunction "T_VCP_TX_14") (pintype "passive"))
      (node (ref "R280") (pin "2") (pintype "passive"))
    )
    (net (code "17") (name "/CONN_nRST") (class "Default")
      (node (ref "J1") (pin "12") (pinfunction "T_nRST_12") (pintype "passive"))
      (node (ref "R32") (pin "2") (pintype "passive"))
      (node (ref "S2") (pin "2") (pintype "passive"))
    )
    (net (code "18") (name "/DAC1") (class "Default")
      (node (ref "C3") (pin "1") (pintype "passive"))
      (node (ref "R8") (pin "2") (pintype "passive"))
      (node (ref "TP1") (pin "1") (pintype "passive"))
    )
    (net (code "19") (name "/DAC2") (class "Default")
      (node (ref "C11") (pin "1") (pintype "passive"))
      (node (ref "R12") (pin "2") (pintype "passive"))
      (node (ref "TP2") (pin "1") (pintype "passive"))
    )
    (net (code "20") (name "/DIP0") (class "Default")
      (node (ref "S1") (pin "1") (pintype "passive"))
      (node (ref "U1") (pin "C10") (pinfunction "PK5_C10") (pintype "passive"))
    )
    (net (code "21") (name "/DIP1") (class "Default")
      (node (ref "S1") (pin "3") (pintype "passive"))
      (node (ref "U1") (pin "A11") (pinfunction "PK6_A11") (pintype "passive"))
    )
    (net (code "22") (name "/DIP2") (class "Default")
      (node (ref "S1") (pin "5") (pintype "passive"))
      (node (ref "U1") (pin "B10") (pinfunction "PK7_B10") (pintype "passive"))
    )
    (net (code "23") (name "/DIP3") (class "Default")
      (node (ref "S1") (pin "7") (pintype "passive"))
      (node (ref "U1") (pin "D9") (pinfunction "PK8_D9") (pintype "passive"))
    )
    (net (code "24") (name "/FDCAN1.RX") (class "Default")
      (node (ref "U1") (pin "C6") (pinfunction "PB8_C6") (pintype "passive"))
    )
    (net (code "25") (name "/FDCAN1.TX") (class "Default") (node (ref "R1") (pin "1") (pintype "passive")))
    (net (code "26") (name "/FDCAN2.RX") (class "Default")
      (node (ref "U1") (pin "P15") (pinfunction "PD9_P15") (pintype "passive"))
    )
    (net (code "27") (name "/FDCAN2.TX") (class "Default") (node (ref "R33") (pin "1") (pintype "passive")))
    (net (code "28") (name "/I2C1.SCL") (class "Default")
      (node (ref "R36") (pin "1") (pintype "passive"))
      (node (ref "R97") (pin "1") (pintype "passive"))
    )
    (net (code "29") (name "/I2C1.SDA") (class "Default")
      (node (ref "R35") (pin "1") (pintype "passive"))
      (node (ref "R54") (pin "1") (pintype "passive"))
    )
    (net (code "30") (name "/LED0") (class "Default")
      (node (ref "R10") (pin "2") (pintype "passive"))
      (node (ref "U1") (pin "A4") (pinfunction "PI5_A4") (pintype "passive"))
    )
    (net (code "31") (name "/LED1") (class "Default")
      (node (ref "R13") (pin "2") (pintype "passive"))
      (node (ref "U1") (pin "A3") (pinfunction "PI6_A3") (pintype "passive"))
    )
    (net (code "32") (name "/LED2") (class "Default")
      (node (ref "R14") (pin "2") (pintype "passive"))
      (node (ref "U1") (pin "B4") (pinfunction "PI7_B4") (pintype "passive"))
    )
    (net (code "33") (name "/MCU_RMII.CRS_DV") (class "Default")
      (node (ref "U1") (pin "P3") (pinfunction "PA7_P3") (pintype "passive"))
    )
    (net (code "34") (name "/MCU_RMII.RXD0") (class "Default")
      (node (ref "U1") (pin "N4") (pinfunction "PC4_N4") (pintype "passive"))
    )
    (net (code "35") (name "/MCU_RMII.RXD1") (class "Default")
      (node (ref "U1") (pin "M5") (pinfunction "PC5_M5") (pintype "passive"))
    )
    (net (code "36") (name "/MCU_RMII.TXD0") (class "Default")
      (node (ref "R40") (pin "1") (pintype "passive"))
    )
    (net (code "37") (name "/MCU_RMII.TXD1") (class "Default")
      (node (ref "R41") (pin "1") (pintype "passive"))
    )
    (net (code "38") (name "/MCU_RMII.TX_EN") (class "Default")
      (node (ref "R38") (pin "1") (pintype "passive"))
    )
    (net (code "39") (name "/MCU_nRST") (class "Default")
      (node (ref "C14") (pin "1") (pintype "passive"))
      (node (ref "R30") (pin "2") (pintype "passive"))
      (node (ref "R32") (pin "1") (pintype "passive"))
      (node (ref "U1") (pin "J5") (pinfunction "NRST_J5") (pintype "passive"))
    )
    (net (code "40") (name "/OSC_IN") (class "Default")
      (node (ref "C16") (pin "1") (pintype "passive"))
      (node (ref "U1") (pin "J1") (pinfunction "OSC_IN_/_PH0_J1") (pintype "passive"))
      (node (ref "X1") (pin "3") (pinfunction "3_3") (pintype "passive"))
    )
    (net (code "41") (name "/OSC_OUT") (class "Default")
      (node (ref "R42") (pin "1") (pintype "passive"))
      (node (ref "U1") (pin "J2") (pinfunction "OSC_OUT_/_PH1_J2") (pintype "passive"))
    )
    (net (code "42") (name "/OUT") (class "Default")
      (node (ref "C177") (pin "1") (pintype "passive"))
      (node (ref "C180") (pin "1") (pintype "passive"))
      (node (ref "U1") (pin "K5") (pinfunction "VREFP_K5") (pintype "passive"))
    )
    (net (code "43") (name "/PA0_TIM2-CH1") (class "Default")
      (node (ref "U1") (pin "L2") (pinfunction "WKUP_/_PA0_L2") (pintype "passive"))
    )
    (net (code "44") (name "/PA1_REFCLK") (class "Default")
      (node (ref "U1") (pin "L4") (pinfunction "PA1_L4") (pintype "passive"))
    )
    (net (code "45") (name "/PA3_ADCx-INP15") (class "Default")
      (node (ref "U1") (pin "M4") (pinfunction "PA3_M4") (pintype "passive"))
    )
    (net (code "46") (name "/PA6_ADCx-INP3") (class "Default")
      (node (ref "U1") (pin "R2") (pinfunction "PA6_R2") (pintype "passive"))
    )
    (net (code "47") (name "/PA8_TIM1-CH1") (class "Default")
      (node (ref "R11") (pin "1") (pintype "passive"))
    )
    (net (code "48") (name "/PC3_ADCx-INP13") (class "Default")
      (node (ref "U1") (pin "M2") (pinfunction "PC3_M2") (pintype "passive"))
    )
    (net (code "49") (name "/PC6_TIM3-CH1") (class "Default")
      (node (ref "R31") (pin "1") (pintype "passive"))
    )
    (net (code "50") (name "/PC7_TIM3-CH2") (class "Default")
      (node (ref "R34") (pin "1") (pintype "passive"))
    )
    (net (code "51") (name "/PD3_EXTI3") (class "Default")
      (node (ref "U1") (pin "A14") (pinfunction "PD3_A14") (pintype "passive"))
    )
    (net (code "52") (name "/PD4_EXTI4") (class "Default")
      (node (ref "U1") (pin "B13") (pinfunction "PD4_B13") (pintype "passive"))
    )
    (net (code "53") (name "/PD12_TIM4-CH1") (class "Default")
      (node (ref "R15") (pin "1") (pintype "passive"))
    )
    (net (code "54") (name "/PD13_TIM4-CH2") (class "Default")
      (node (ref "R16") (pin "1") (pintype "passive"))
    )
    (net (code "55") (name "/PD14_TIM4-CH3") (class "Default")
      (node (ref "R17") (pin "1") (pintype "passive"))
    )
    (net (code "56") (name "/PE2") (class "Default") (node (ref "R6") (pin "1") (pintype "passive")))
    (net (code "57") (name "/PE3") (class "Default")
      (node (ref "U1") (pin "D5") (pinfunction "PE3_D5") (pintype "passive"))
    )
    (net (code "58") (name "/PE10") (class "Default") (node (ref "R28") (pin "1") (pintype "passive")))
    (net (code "59") (name "/PE11_SPI4-nSS") (class "Default")
      (node (ref "R29") (pin "1") (pintype "passive"))
    )
    (net (code "60") (name "/PE15_EXTI15") (class "Default")
      (node (ref "U1") (pin "R11") (pinfunction "PE15_R11") (pintype "passive"))
    )
    (net (code "61") (name "/PF6_SPI5-nSS") (class "Default")
      (node (ref "R258") (pin "1") (pintype "passive"))
    )
    (net (code "62") (name "/PF13") (class "Default")
      (node (ref "U1") (pin "R6") (pinfunction "PF13_R6") (pintype "passive"))
    )
    (net (code "63") (name "/PF14") (class "Default")
      (node (ref "U1") (pin "M7") (pinfunction "PF14_M7") (pintype "passive"))
    )
    (net (code "64") (name "/PF15") (class "Default")
      (node (ref "U1") (pin "N7") (pinfunction "PF15_N7") (pintype "passive"))
    )
    (net (code "65") (name "/PG2") (class "Default")
      (node (ref "U1") (pin "L15") (pinfunction "PG2_L15") (pintype "passive"))
    )
    (net (code "66") (name "/PG3") (class "Default")
      (node (ref "U1") (pin "J12") (pinfunction "PG3_J12") (pintype "passive"))
    )
    (net (code "67") (name "/PG4") (class "Default")
      (node (ref "U1") (pin "K14") (pinfunction "PG4_K14") (pintype "passive"))
    )
    (net (code "68") (name "/PG5") (class "Default")
      (node (ref "U1") (pin "K15") (pinfunction "PG5_K15") (pintype "passive"))
    )
    (net (code "69") (name "/PG8_SPI6-nSS") (class "Default")
      (node (ref "R18") (pin "1") (pintype "passive"))
    )
    (net (code "70") (name "/PH2") (class "Default") (node (ref "R259") (pin "1") (pintype "passive")))
    (net (code "71") (name "/PH3") (class "Default") (node (ref "R99") (pin "1") (pintype "passive")))
    (net (code "72") (name "/PH6_TIM12-CH1") (class "Default")
      (node (ref "R337") (pin "2") (pintype "passive"))
      (node (ref "U1") (pin "N11") (pinfunction "PH6_N11") (pintype "passive"))
    )
    (net (code "73") (name "/PH9_TIM12-CH2") (class "Default")
      (node (ref "U1") (pin "P13") (pinfunction "PH9_P13") (pintype "passive"))
    )
    (net (code "74") (name "/PH13") (class "Default") (node (ref "R260") (pin "1") (pintype "passive")))
    (net (code "75") (name "/PH14") (class "Default") (node (ref "R262") (pin "1") (pintype "passive")))
    (net (code "76") (name "/PH15") (class "Default") (node (ref "R261") (pin "1") (pintype "passive")))
    (net (code "77") (name "/PI8") (class "Default")
      (node (ref "R322") (pin "2") (pintype "passive"))
      (node (ref "U1") (pin "E4") (pinfunction "PI8_E4") (pintype "passive"))
    )
    (net (code "78") (name "/PI9_EXTI9") (class "Default")
      (node (ref "R323") (pin "2") (pintype "passive"))
      (node (ref "U1") (pin "E2") (pinfunction "PI9_E2") (pintype "passive"))
    )
    (net (code "79") (name "/PJ0") (class "Default") (node (ref "R45") (pin "1") (pintype "passive")))
    (net (code "80") (name "/PJ1") (class "Default") (node (ref "R287") (pin "1") (pintype "passive")))
    (net (code "81") (name "/PJ2") (class "Default")
      (node (ref "R332") (pin "1") (pintype "passive"))
      (node (ref "U1") (pin "P5") (pinfunction "PJ2_P5") (pintype "passive"))
    )
    (net (code "82") (name "/PJ3") (class "Default")
      (node (ref "U1") (pin "R5") (pinfunction "PJ3_R5") (pintype "passive"))
    )
    (net (code "83") (name "/PJ4") (class "Default")
      (node (ref "U1") (pin "N6") (pinfunction "PJ4_N6") (pintype "passive"))
    )
    (net (code "84") (name "/PJ5") (class "Default")
      (node (ref "U1") (pin "P8") (pinfunction "PJ5_P8") (pintype "passive"))
    )
    (net (code "85") (name "/PJ6") (class "Default")
      (node (ref "U1") (pin "R8") (pinfunction "PJ6_R8") (pintype "passive"))
    )
    (net (code "86") (name "/PJ7_TIM5-CH1") (class "Default")
      (node (ref "U1") (pin "R9") (pinfunction "PJ7_R9") (pintype "passive"))
    )
    (net (code "87") (name "/PJ8") (class "Default")
      (node (ref "U1") (pin "P9") (pinfunction "PJ8_P9") (pintype "passive"))
    )
    (net (code "88") (name "/PJ9") (class "Default")
      (node (ref "U1") (pin "N9") (pinfunction "PJ9_N9") (pintype "passive"))
    )
    (net (code "89") (name "/PJ13_EXTI13") (class "Default")
      (node (ref "U1") (pin "C11") (pinfunction "PJ13_C11") (pintype "passive"))
    )
    (net (code "90") (name "/PJ14_EXTI14") (class "Default")
      (node (ref "R4") (pin "2") (pintype "passive"))
      (node (ref "U1") (pin "D10") (pinfunction "PJ14_D10") (pintype "passive"))
    )
    (net (code "91") (name "/PJ15") (class "Default") (node (ref "R5") (pin "1") (pintype "passive")))
    (net (code "92") (name "/PK9") (class "Default") (node (ref "R53") (pin "1") (pintype "passive")))
    (net (code "93") (name "/PK10") (class "Default") (node (ref "R46") (pin "1") (pintype "passive")))
    (net (code "94") (name "/PK11_EXTI11") (class "Default")
      (node (ref "U1") (pin "C2") (pinfunction "PK11_C2") (pintype "passive"))
    )
    (net (code "95") (name "/SAI1_I2S.FS") (class "Default")
      (node (ref "R319") (pin "1") (pintype "passive"))
    )
    (net (code "96") (name "/SAI1_I2S.MCLK") (class "Default")
      (node (ref "R324") (pin "1") (pintype "passive"))
    )
    (net (code "97") (name "/SAI1_I2S.SCK") (class "Default")
      (node (ref "R320") (pin "1") (pintype "passive"))
    )
    (net (code "98") (name "/SAI1_I2S.SD") (class "Default")
      (node (ref "R321") (pin "1") (pintype "passive"))
    )
    (net (code "99") (name "/SDIO.CLK") (class "Default") (node (ref "R51") (pin "1") (pintype "passive")))
    (net (code "100") (name "/SDIO.CMD") (class "Default") (node (ref "R2") (pin "1") (pintype "passive")))
    (net (code "101") (name "/SDIO.D0") (class "Default") (node (ref "R47") (pin "1") (pintype "passive")))
    (net (code "102") (name "/SDIO.D1") (class "Default") (node (ref "R48") (pin "1") (pintype "passive")))
    (net (code "103") (name "/SDIO.D2") (class "Default") (node (ref "R49") (pin "1") (pintype "passive")))
    (net (code "104") (name "/SDIO.D3") (class "Default") (node (ref "R50") (pin "1") (pintype "passive")))
    (net (code "105") (name "/SMI.MDC") (class "Default") (node (ref "R95") (pin "1") (pintype "passive")))
    (net (code "106") (name "/SMI.MDIO") (class "Default")
      (node (ref "R52") (pin "1") (pintype "passive"))
      (node (ref "U1") (pin "M3") (pinfunction "PA2_M3") (pintype "passive"))
    )
    (net (code "107") (name "/SPI2.MISO") (class "Default")
      (node (ref "U1") (pin "F10") (pinfunction "PI2_F10") (pintype "passive"))
    )
    (net (code "108") (name "/SPI2.MOSI") (class "Default") (node (ref "R44") (pin "1") (pintype "passive")))
    (net (code "109") (name "/SPI2.SCK") (class "Default") (node (ref "R3") (pin "1") (pintype "passive")))
    (net (code "110") (name "/SPI4.MISO") (class "Default")
      (node (ref "U1") (pin "P10") (pinfunction "PE13_P10") (pintype "passive"))
    )
    (net (code "111") (name "/SPI4.MOSI") (class "Default") (node (ref "R43") (pin "1") (pintype "passive")))
    (net (code "112") (name "/SPI4.SCK") (class "Default") (node (ref "R25") (pin "1") (pintype "passive")))
    (net (code "113") (name "/SPI5.MISO") (class "Default")
      (node (ref "U1") (pin "H1") (pinfunction "PF8_H1") (pintype "passive"))
    )
    (net (code "114") (name "/SPI5.MOSI") (class "Default") (node (ref "R7") (pin "1") (pintype "passive")))
    (net (code "115") (name "/SPI5.SCK") (class "Default") (node (ref "R27") (pin "1") (pintype "passive")))
    (net (code "116") (name "/SPI6.MISO") (class "Default")
      (node (ref "U1") (pin "C8") (pinfunction "PG12_C8") (pintype "passive"))
    )
    (net (code "117") (name "/SPI6.MOSI") (class "Default") (node (ref "R23") (pin "1") (pintype "passive")))
    (net (code "118") (name "/SPI6.SCK") (class "Default") (node (ref "R19") (pin "1") (pintype "passive")))
    (net (code "119") (name "/SWD.SWCLK") (class "Default")
      (node (ref "R26") (pin "1") (pintype "passive"))
      (node (ref "U1") (pin "C15") (pinfunction "JTCK_/_SWCLK_/_PA14_C15") (pintype "passive"))
    )
    (net (code "120") (name "/SWD.SWDIO") (class "Default")
      (node (ref "R22") (pin "1") (pintype "passive"))
      (node (ref "U1") (pin "F12") (pinfunction "JTMS_/_SWDIO_/_PA13_F12") (pintype "passive"))
    )
    (net (code "121") (name "/SWD.SWO") (class "Default")
      (node (ref "R56") (pin "1") (pintype "passive"))
      (node (ref "U1") (pin "B7") (pinfunction "JTDO_/_SWO_/_PB3_B7") (pintype "passive"))
    )
    (net (code "122") (name "/UART7.RX") (class "Default")
      (node (ref "U1") (pin "L8") (pinfunction "PE7_L8") (pintype "passive"))
    )
    (net (code "123") (name "/UART7.TX") (class "Default") (node (ref "R37") (pin "1") (pintype "passive")))
    (net (code "124") (name "/UART8.RX") (class "Default")
      (node (ref "U1") (pin "D6") (pinfunction "PE0_D6") (pintype "passive"))
    )
    (net (code "125") (name "/UART8.TX") (class "Default") (node (ref "R21") (pin "1") (pintype "passive")))
    (net (code "126") (name "/USART2.RX") (class "Default")
      (node (ref "U1") (pin "A10") (pinfunction "PD6_A10") (pintype "passive"))
    )
    (net (code "127") (name "/USART2.TX") (class "Default") (node (ref "R294") (pin "1") (pintype "passive")))
    (net (code "128") (name "/USART3_RX") (class "Default")
      (node (ref "R263") (pin "1") (pintype "passive"))
      (node (ref "U1") (pin "P11") (pinfunction "PB11_P11") (pintype "passive"))
    )
    (net (code "129") (name "/USART3_TX") (class "Default")
      (node (ref "R280") (pin "1") (pintype "passive"))
      (node (ref "U1") (pin "M10") (pinfunction "PB10_M10") (pintype "passive"))
    )
    (net (code "130") (name "/USB_DFP1._N") (class "Default")
      (node (ref "U1") (pin "F15") (pinfunction "PA11_F15") (pintype "passive"))
    )
    (net (code "131") (name "/USB_DFP1._P") (class "Default")
      (node (ref "U1") (pin "F14") (pinfunction "PA12_F14") (pintype "passive"))
    )
    (net (code "142") (name "1P1_MCU") (class "Default")
      (node (ref "C1") (pin "1") (pintype "passive"))
      (node (ref "C12") (pin "1") (pintype "passive"))
      (node (ref "C2") (pin "1") (pintype "passive"))
      (node (ref "L5") (pin "2") (pintype "passive"))
      (node (ref "U1") (pin "E6") (pinfunction "VCAP2_E6") (pintype "passive"))
      (node (ref "U1") (pin "L10") (pinfunction "VCAP1_L10") (pintype "passive"))
    )
    (net (code "143") (name "3P3") (class "Default")
      (node (ref "C10") (pin "1") (pintype "passive"))
      (node (ref "C13") (pin "1") (pintype "passive"))
      (node (ref "C4") (pin "1") (pintype "passive"))
      (node (ref "C43") (pin "1") (pintype "passive"))
      (node (ref "C45") (pin "1") (pintype "passive"))
      (node (ref "C5") (pin "1") (pintype "passive"))
      (node (ref "C6") (pin "1") (pintype "passive"))
      (node (ref "C63") (pin "1") (pintype "passive"))
      (node (ref "C64") (pin "1") (pintype "passive"))
      (node (ref "C65") (pin "1") (pintype "passive"))
      (node (ref "C66") (pin "1") (pintype "passive"))
      (node (ref "C69") (pin "1") (pintype "passive"))
      (node (ref "C75") (pin "1") (pintype "passive"))
      (node (ref "C8") (pin "1") (pintype "passive"))
      (node (ref "C9") (pin "1") (pintype "passive"))
      (node (ref "D1") (pin "2") (pintype "passive"))
      (node (ref "D45") (pin "2") (pintype "passive"))
      (node (ref "D46") (pin "1") (pintype "passive"))
      (node (ref "FB2") (pin "2") (pintype "passive"))
      (node (ref "R20") (pin "2") (pintype "passive"))
      (node (ref "R30") (pin "1") (pintype "passive"))
      (node (ref "R312") (pin "1") (pintype "passive"))
      (node (ref "R323") (pin "1") (pintype "passive"))
      (node (ref "R332") (pin "2") (pintype "passive"))
      (node (ref "R4") (pin "1") (pintype "passive"))
      (node (ref "R52") (pin "2") (pintype "passive"))
      (node (ref "R54") (pin "2") (pintype "passive"))
      (node (ref "R97") (pin "2") (pintype "passive"))
      (node (ref "S3") (pin "2") (pintype "passive"))
      (node (ref "U1") (pin "D7") (pinfunction "VDDIO2_D7") (pintype "passive"))
      (node (ref "U1") (pin "F11") (pinfunction "VDDUSB_F11") (pintype "passive"))
      (node (ref "U1") (pin "F7") (pinfunction "VDD_F7") (pintype "passive"))
      (node (ref "U1") (pin "F9") (pinfunction "VDD_F9") (pintype "passive"))
      (node (ref "U1") (pin "G10") (pinfunction "VDD_G10") (pintype "passive"))
      (node (ref "U1") (pin "G6") (pinfunction "VDD_G6") (pintype "passive"))
      (node (ref "U1") (pin "G7") (pinfunction "VDD_G7") (pintype "passive"))
      (node (ref "U1") (pin "G9") (pinfunction "VDD_G9") (pintype "passive"))
      (node (ref "U1") (pin "J10") (pinfunction "VDD_J10") (pintype "passive"))
      (node (ref "U1") (pin "J6") (pinfunction "VDD_J6") (pintype "passive"))
      (node (ref "U1") (pin "J7") (pinfunction "VDD_J7") (pintype "passive"))
      (node (ref "U1") (pin "J9") (pinfunction "VDD_J9") (pintype "passive"))
      (node (ref "U1") (pin "K7") (pinfunction "VDD_K7") (pintype "passive"))
      (node (ref "U1") (pin "K9") (pinfunction "VDD_K9") (pintype "passive"))
      (node (ref "U1") (pin "R13") (pinfunction "VDDSMPS_R13") (pintype "passive"))
    )
    (net (code "144") (name "GND") (class "Default")
      (node (ref "C1") (pin "2") (pintype "passive"))
      (node (ref "C10") (pin "2") (pintype "passive"))
      (node (ref "C11") (pin "2") (pintype "passive"))
      (node (ref "C12") (pin "2") (pintype "passive"))
      (node (ref "C13") (pin "2") (pintype "passive"))
      (node (ref "C14") (pin "2") (pintype "passive"))
      (node (ref "C15") (pin "2") (pintype "passive"))
      (node (ref "C16") (pin "2") (pintype "passive"))
      (node (ref "C169") (pin "2") (pintype "passive"))
      (node (ref "C17") (pin "2") (pintype "passive"))
      (node (ref "C177") (pin "2") (pintype "passive"))
      (node (ref "C18") (pin "2") (pintype "passive"))
      (node (ref "C180") (pin "2") (pintype "passive"))
      (node (ref "C2") (pin "2") (pintype "passive"))
      (node (ref "C3") (pin "2") (pintype "passive"))
      (node (ref "C4") (pin "2") (pintype "passive"))
      (node (ref "C43") (pin "2") (pintype "passive"))
      (node (ref "C45") (pin "2") (pintype "passive"))
      (node (ref "C5") (pin "2") (pintype "passive"))
      (node (ref "C6") (pin "2") (pintype "passive"))
      (node (ref "C63") (pin "2") (pintype "passive"))
      (node (ref "C64") (pin "2") (pintype "passive"))
      (node (ref "C65") (pin "2") (pintype "passive"))
      (node (ref "C66") (pin "2") (pintype "passive"))
      (node (ref "C67") (pin "2") (pintype "passive"))
      (node (ref "C68") (pin "2") (pintype "passive"))
      (node (ref "C69") (pin "2") (pintype "passive"))
      (node (ref "C7") (pin "2") (pintype "passive"))
      (node (ref "C75") (pin "2") (pintype "passive"))
      (node (ref "C76") (pin "1") (pintype "passive"))
      (node (ref "C8") (pin "2") (pintype "passive"))
      (node (ref "C9") (pin "2") (pintype "passive"))
      (node (ref "D45") (pin "1") (pintype "passive"))
      (node (ref "J1") (pin "11") (pinfunction "GNDdetect_11") (pintype "passive"))
      (node (ref "J1") (pin "5") (pinfunction "GND_5") (pintype "passive"))
      (node (ref "J1") (pin "7") (pinfunction "GND_7") (pintype "passive"))
      (node (ref "Q12") (pin "2") (pinfunction "E_2") (pintype "passive"))
      (node (ref "R322") (pin "1") (pintype "passive"))
      (node (ref "R39") (pin "2") (pintype "passive"))
      (node (ref "S1") (pin "2") (pintype "passive"))
      (node (ref "S1") (pin "4") (pintype "passive"))
      (node (ref "S1") (pin "6") (pintype "passive"))
      (node (ref "S1") (pin "8") (pintype "passive"))
      (node (ref "S2") (pin "1") (pintype "passive"))
      (node (ref "TP52") (pin "1") (pintype "passive"))
      (node (ref "U1") (pin "A1") (pinfunction "VSS_A1") (pintype "passive"))
      (node (ref "U1") (pin "A15") (pinfunction "VSS_A15") (pintype "passive"))
      (node (ref "U1") (pin "E11") (pinfunction "VSS_E11") (pintype "passive"))
      (node (ref "U1") (pin "E3") (pinfunction "VSS_E3") (pintype "passive"))
      (node (ref "U1") (pin "E5") (pinfunction "VSS_E5") (pintype "passive"))
      (node (ref "U1") (pin "F8") (pinfunction "VSS_F8") (pintype "passive"))
      (node (ref "U1") (pin "G12") (pinfunction "VSSUSB_G12") (pintype "passive"))
      (node (ref "U1") (pin "G8") (pinfunction "VSS_G8") (pintype "passive"))
      (node (ref "U1") (pin "H10") (pinfunction "VSS_H10") (pintype "passive"))
      (node (ref "U1") (pin "H12") (pinfunction "VDD11USB_H12") (pintype "passive"))
      (node (ref "U1") (pin "H6") (pinfunction "VSS_H6") (pintype "passive"))
      (node (ref "U1") (pin "H7") (pinfunction "VSS_H7") (pintype "passive"))
      (node (ref "U1") (pin "H8") (pinfunction "VSS_H8") (pintype "passive"))
      (node (ref "U1") (pin "H9") (pinfunction "VSS_H9") (pintype "passive"))
      (node (ref "U1") (pin "J3") (pinfunction "VSS_J3") (pintype "passive"))
      (node (ref "U1") (pin "J8") (pinfunction "VSS_J8") (pintype "passive"))
      (node (ref "U1") (pin "K3") (pinfunction "VSSA_K3") (pintype "passive"))
      (node (ref "U1") (pin "K4") (pinfunction "VREFM_K4") (pintype "passive"))
      (node (ref "U1") (pin "K8") (pinfunction "VSS_K8") (pintype "passive"))
      (node (ref "U1") (pin "L11") (pinfunction "VSS_L11") (pintype "passive"))
      (node (ref "U1") (pin "L5") (pinfunction "VSS_L5") (pintype "passive"))
      (node (ref "U1") (pin "P12") (pinfunction "VSSSMPS_P12") (pintype "passive"))
      (node (ref "U1") (pin "R1") (pinfunction "VSS_R1") (pintype "passive"))
      (node (ref "U1") (pin "R15") (pinfunction "VSS_R15") (pintype "passive"))
      (node (ref "X1") (pin "2") (pinfunction "2_2") (pintype "passive"))
      (node (ref "X1") (pin "4") (pinfunction "4_4") (pintype "passive"))
    )
    (net (code "145") (name "Net-(C15-Pad1)") (class "Default")
      (node (ref "C15") (pin "1") (pintype "passive"))
      (node (ref "R42") (pin "2") (pintype "passive"))
      (node (ref "X1") (pin "1") (pinfunction "1_1") (pintype "passive"))
    )
    (net (code "146") (name "Net-(C18-Pad1)") (class "Default")
      (node (ref "C18") (pin "1") (pintype "passive"))
      (node (ref "R55") (pin "2") (pintype "passive"))
      (node (ref "X2") (pin "1") (pinfunction "1_1") (pintype "passive"))
    )
    (net (code "147") (name "Net-(C67-Pad1)") (class "Default")
      (node (ref "C67") (pin "1") (pintype "passive"))
      (node (ref "R9") (pin "1") (pintype "passive"))
    )
    (net (code "148") (name "Net-(D1-Pad1)") (class "Default")
      (node (ref "D1") (pin "1") (pintype "passive"))
      (node (ref "R14") (pin "1") (pintype "passive"))
    )
    (net (code "149") (name "Net-(D1-Pad3)") (class "Default")
      (node (ref "D1") (pin "3") (pintype "passive"))
      (node (ref "R13") (pin "1") (pintype "passive"))
    )
    (net (code "150") (name "Net-(D1-Pad4)") (class "Default")
      (node (ref "D1") (pin "4") (pintype "passive"))
      (node (ref "R10") (pin "1") (pintype "passive"))
    )
    (net (code "151") (name "Net-(D46-Pad2)") (class "Default")
      (node (ref "D46") (pin "2") (pintype "passive"))
      (node (ref "R154") (pin "1") (pintype "passive"))
    )
    (net (code "152") (name "Net-(J1-T_VCC)") (class "Default")
      (node (ref "J1") (pin "3") (pinfunction "T_VCC_3") (pintype "passive"))
      (node (ref "R20") (pin "1") (pintype "passive"))
    )
    (net (code "153") (name "Net-(Q12-B)") (class "Default")
      (node (ref "Q12") (pin "1") (pinfunction "B_1") (pintype "passive"))
      (node (ref "R337") (pin "1") (pintype "passive"))
    )
    (net (code "154") (name "Net-(Q12-C)") (class "Default")
      (node (ref "Q12") (pin "3") (pinfunction "C_3") (pintype "passive"))
      (node (ref "R154") (pin "2") (pintype "passive"))
    )
    (net (code "155") (name "Net-(R254-Pad2)") (class "Default")
      (node (ref "R254") (pin "2") (pintype "passive"))
      (node (ref "TP51") (pin "1") (pintype "passive"))
    )
    (net (code "156") (name "Net-(U1A-PA4)") (class "Default")
      (node (ref "R8") (pin "1") (pintype "passive"))
      (node (ref "U1") (pin "N3") (pinfunction "PA4_N3") (pintype "passive"))
    )
    (net (code "157") (name "Net-(U1A-PA5)") (class "Default")
      (node (ref "R12") (pin "1") (pintype "passive"))
      (node (ref "U1") (pin "P2") (pinfunction "PA5_P2") (pintype "passive"))
    )
    (net (code "158") (name "Net-(U1A-PA8)") (class "Default")
      (node (ref "R11") (pin "2") (pintype "passive"))
      (node (ref "U1") (pin "G11") (pinfunction "PA8_G11") (pintype "passive"))
    )
    (net (code "159") (name "Net-(U1B-PB0)") (class "Default")
      (node (ref "C169") (pin "1") (pintype "passive"))
      (node (ref "D45") (pin "3") (pintype "passive"))
      (node (ref "R254") (pin "1") (pintype "passive"))
      (node (ref "U1") (pin "R3") (pinfunction "PB0_R3") (pintype "passive"))
    )
    (net (code "160") (name "Net-(U1B-PB6)") (class "Default")
      (node (ref "R36") (pin "2") (pintype "passive"))
      (node (ref "U1") (pin "E8") (pinfunction "PB6_E8") (pintype "passive"))
    )
    (net (code "161") (name "Net-(U1B-PB7)") (class "Default")
      (node (ref "R35") (pin "2") (pintype "passive"))
      (node (ref "U1") (pin "A6") (pinfunction "PB7_A6") (pintype "passive"))
    )
    (net (code "162") (name "Net-(U1B-PB9)") (class "Default")
      (node (ref "R1") (pin "2") (pintype "passive"))
      (node (ref "U1") (pin "A5") (pinfunction "PB9_A5") (pintype "passive"))
    )
    (net (code "163") (name "Net-(U1B-PB12)") (class "Default")
      (node (ref "R40") (pin "2") (pintype "passive"))
      (node (ref "U1") (pin "P14") (pinfunction "PB12_P14") (pintype "passive"))
    )
    (net (code "164") (name "Net-(U1B-PB13)") (class "Default")
      (node (ref "R33") (pin "2") (pintype "passive"))
      (node (ref "U1") (pin "N13") (pinfunction "PB13_N13") (pintype "passive"))
    )
    (net (code "165") (name "Net-(U1B-PB15)") (class "Default")
      (node (ref "R41") (pin "2") (pintype "passive"))
      (node (ref "U1") (pin "M13") (pinfunction "PB15_M13") (pintype "passive"))
    )
    (net (code "166") (name "Net-(U1C-OSC32_IN_{slash}_PC14)") (class "Default")
      (node (ref "C17") (pin "1") (pintype "passive"))
      (node (ref "U1") (pin "D2") (pinfunction "OSC32_IN_/_PC14_D2") (pintype "passive"))
      (node (ref "X2") (pin "2") (pinfunction "2_2") (pintype "passive"))
    )
    (net (code "167") (name "Net-(U1C-OSC32_OUT_{slash}_PC15)") (class "Default")
      (node (ref "R55") (pin "1") (pintype "passive"))
      (node (ref "U1") (pin "D1") (pinfunction "OSC32_OUT_/_PC15_D1") (pintype "passive"))
    )
    (net (code "168") (name "Net-(U1C-PC1)") (class "Default")
      (node (ref "R95") (pin "2") (pintype "passive"))
      (node (ref "U1") (pin "K2") (pinfunction "PC1_K2") (pintype "passive"))
    )
    (net (code "169") (name "Net-(U1C-PC6)") (class "Default")
      (node (ref "R31") (pin "2") (pintype "passive"))
      (node (ref "U1") (pin "J15") (pinfunction "PC6_J15") (pintype "passive"))
    )
    (net (code "170") (name "Net-(U1C-PC7)") (class "Default")
      (node (ref "R34") (pin "2") (pintype "passive"))
      (node (ref "U1") (pin "H14") (pinfunction "PC7_H14") (pintype "passive"))
    )
    (net (code "171") (name "Net-(U1C-PC8)") (class "Default")
      (node (ref "R47") (pin "2") (pintype "passive"))
      (node (ref "U1") (pin "H13") (pinfunction "PC8_H13") (pintype "passive"))
    )
    (net (code "172") (name "Net-(U1C-PC9)") (class "Default")
      (node (ref "R48") (pin "2") (pintype "passive"))
      (node (ref "U1") (pin "G14") (pinfunction "PC9_G14") (pintype "passive"))
    )
    (net (code "173") (name "Net-(U1C-PC10)") (class "Default")
      (node (ref "R49") (pin "2") (pintype "passive"))
      (node (ref "U1") (pin "D12") (pinfunction "PC10_D12") (pintype "passive"))
    )
    (net (code "174") (name "Net-(U1C-PC11)") (class "Default")
      (node (ref "R50") (pin "2") (pintype "passive"))
      (node (ref "U1") (pin "B14") (pinfunction "PC11_B14") (pintype "passive"))
    )
    (net (code "175") (name "Net-(U1C-PC12)") (class "Default")
      (node (ref "R51") (pin "2") (pintype "passive"))
      (node (ref "U1") (pin "B15") (pinfunction "PC12_B15") (pintype "passive"))
    )
    (net (code "176") (name "Net-(U1D-PD2)") (class "Default")
      (node (ref "R2") (pin "2") (pintype "passive"))
      (node (ref "U1") (pin "D11") (pinfunction "PD2_D11") (pintype "passive"))
    )
    (net (code "177") (name "Net-(U1D-PD5)") (class "Default")
      (node (ref "R294") (pin "2") (pintype "passive"))
      (node (ref "U1") (pin "B12") (pinfunction "PD5_B12") (pintype "passive"))
    )
    (net (code "178") (name "Net-(U1D-PD12)") (class "Default")
      (node (ref "R15") (pin "2") (pintype "passive"))
      (node (ref "U1") (pin "M14") (pinfunction "PD12_M14") (pintype "passive"))
    )
    (net (code "179") (name "Net-(U1D-PD13)") (class "Default")
      (node (ref "R16") (pin "2") (pintype "passive"))
      (node (ref "U1") (pin "L13") (pinfunction "PD13_L13") (pintype "passive"))
    )
    (net (code "180") (name "Net-(U1D-PD14)") (class "Default")
      (node (ref "R17") (pin "2") (pintype "passive"))
      (node (ref "U1") (pin "J11") (pinfunction "PD14_J11") (pintype "passive"))
    )
    (net (code "181") (name "Net-(U1E-PE1)") (class "Default")
      (node (ref "R21") (pin "2") (pintype "passive"))
      (node (ref "U1") (pin "B5") (pinfunction "PE1_B5") (pintype "passive"))
    )
    (net (code "182") (name "Net-(U1E-PE2)") (class "Default")
      (node (ref "R6") (pin "2") (pintype "passive"))
      (node (ref "U1") (pin "B3") (pinfunction "PE2_B3") (pintype "passive"))
    )
    (net (code "183") (name "Net-(U1E-PE4)") (class "Default")
      (node (ref "R319") (pin "2") (pintype "passive"))
      (node (ref "U1") (pin "C4") (pinfunction "PE4_C4") (pintype "passive"))
    )
    (net (code "184") (name "Net-(U1E-PE5)") (class "Default")
      (node (ref "R320") (pin "2") (pintype "passive"))
      (node (ref "U1") (pin "D4") (pinfunction "PE5_D4") (pintype "passive"))
    )
    (net (code "185") (name "Net-(U1E-PE6)") (class "Default")
      (node (ref "R321") (pin "2") (pintype "passive"))
      (node (ref "U1") (pin "F6") (pinfunction "PE6_F6") (pintype "passive"))
    )
    (net (code "186") (name "Net-(U1E-PE8)") (class "Default")
      (node (ref "R37") (pin "2") (pintype "passive"))
      (node (ref "U1") (pin "M8") (pinfunction "PE8_M8") (pintype "passive"))
    )
    (net (code "187") (name "Net-(U1E-PE10)") (class "Default")
      (node (ref "R28") (pin "2") (pintype "passive"))
      (node (ref "U1") (pin "M9") (pinfunction "PE10_M9") (pintype "passive"))
    )
    (net (code "188") (name "Net-(U1E-PE11)") (class "Default")
      (node (ref "R29") (pin "2") (pintype "passive"))
      (node (ref "U1") (pin "R10") (pinfunction "PE11_R10") (pintype "passive"))
    )
    (net (code "189") (name "Net-(U1E-PE12)") (class "Default")
      (node (ref "R25") (pin "2") (pintype "passive"))
      (node (ref "U1") (pin "L9") (pinfunction "PE12_L9") (pintype "passive"))
    )
    (net (code "190") (name "Net-(U1E-PE14)") (class "Default")
      (node (ref "R43") (pin "2") (pintype "passive"))
      (node (ref "U1") (pin "N10") (pinfunction "PE14_N10") (pintype "passive"))
    )
    (net (code "191") (name "Net-(U1F-PF6)") (class "Default")
      (node (ref "R258") (pin "2") (pintype "passive"))
      (node (ref "U1") (pin "H3") (pinfunction "PF6_H3") (pintype "passive"))
    )
    (net (code "192") (name "Net-(U1F-PF7)") (class "Default")
      (node (ref "R27") (pin "2") (pintype "passive"))
      (node (ref "U1") (pin "H2") (pinfunction "PF7_H2") (pintype "passive"))
    )
    (net (code "193") (name "Net-(U1F-PF9)") (class "Default")
      (node (ref "R7") (pin "2") (pintype "passive"))
      (node (ref "U1") (pin "J4") (pinfunction "PF9_J4") (pintype "passive"))
    )
    (net (code "194") (name "Net-(U1G-PG8)") (class "Default")
      (node (ref "R18") (pin "2") (pintype "passive"))
      (node (ref "U1") (pin "J14") (pinfunction "PG8_J14") (pintype "passive"))
    )
    (net (code "195") (name "Net-(U1G-PG11)") (class "Default")
      (node (ref "R38") (pin "2") (pintype "passive"))
      (node (ref "U1") (pin "D8") (pinfunction "PG11_D8") (pintype "passive"))
    )
    (net (code "196") (name "Net-(U1G-PG13)") (class "Default")
      (node (ref "R19") (pin "2") (pintype "passive"))
      (node (ref "U1") (pin "B8") (pinfunction "PG13_B8") (pintype "passive"))
    )
    (net (code "197") (name "Net-(U1G-PG14)") (class "Default")
      (node (ref "R23") (pin "2") (pintype "passive"))
      (node (ref "U1") (pin "A8") (pinfunction "PG14_A8") (pintype "passive"))
    )
    (net (code "198") (name "Net-(U1H-PH2)") (class "Default")
      (node (ref "R259") (pin "2") (pintype "passive"))
      (node (ref "U1") (pin "N1") (pinfunction "PH2_N1") (pintype "passive"))
    )
    (net (code "199") (name "Net-(U1H-PH3)") (class "Default")
      (node (ref "R99") (pin "2") (pintype "passive"))
      (node (ref "U1") (pin "N2") (pinfunction "PH3_N2") (pintype "passive"))
    )
    (net (code "200") (name "Net-(U1H-PH13)") (class "Default")
      (node (ref "R260") (pin "2") (pintype "passive"))
      (node (ref "U1") (pin "E15") (pinfunction "PH13_E15") (pintype "passive"))
    )
    (net (code "201") (name "Net-(U1H-PH14)") (class "Default")
      (node (ref "R262") (pin "2") (pintype "passive"))
      (node (ref "U1") (pin "E14") (pinfunction "PH14_E14") (pintype "passive"))
    )
    (net (code "202") (name "Net-(U1H-PH15)") (class "Default")
      (node (ref "R261") (pin "2") (pintype "passive"))
      (node (ref "U1") (pin "E13") (pinfunction "PH15_E13") (pintype "passive"))
    )
    (net (code "203") (name "Net-(U1I-PI1)") (class "Default")
      (node (ref "R3") (pin "2") (pintype "passive"))
      (node (ref "U1") (pin "D15") (pinfunction "PI1_D15") (pintype "passive"))
    )
    (net (code "204") (name "Net-(U1I-PI3)") (class "Default")
      (node (ref "R44") (pin "2") (pintype "passive"))
      (node (ref "U1") (pin "D14") (pinfunction "PI3_D14") (pintype "passive"))
    )
    (net (code "205") (name "Net-(U1I-PI11)") (class "Default")
      (node (ref "R324") (pin "2") (pintype "passive"))
      (node (ref "U1") (pin "F3") (pinfunction "PI11_F3") (pintype "passive"))
    )
    (net (code "206") (name "Net-(U1J-PJ0)") (class "Default")
      (node (ref "R45") (pin "2") (pintype "passive"))
      (node (ref "U1") (pin "R4") (pinfunction "PJ0_R4") (pintype "passive"))
    )
    (net (code "207") (name "Net-(U1J-PJ1)") (class "Default")
      (node (ref "R287") (pin "2") (pintype "passive"))
      (node (ref "U1") (pin "M6") (pinfunction "PJ1_M6") (pintype "passive"))
    )
    (net (code "208") (name "Net-(U1J-PJ15)") (class "Default")
      (node (ref "R312") (pin "2") (pintype "passive"))
      (node (ref "R5") (pin "2") (pintype "passive"))
      (node (ref "U1") (pin "E9") (pinfunction "PJ15_E9") (pintype "passive"))
    )
    (net (code "209") (name "Net-(U1K-PK9)") (class "Default")
      (node (ref "R53") (pin "2") (pintype "passive"))
      (node (ref "U1") (pin "A2") (pinfunction "PK9_A2") (pintype "passive"))
    )
    (net (code "210") (name "Net-(U1K-PK10)") (class "Default")
      (node (ref "R46") (pin "2") (pintype "passive"))
      (node (ref "U1") (pin "B2") (pinfunction "PK10_B2") (pintype "passive"))
    )
    (net (code "211") (name "Net-(U1L-VDDA)") (class "Default")
      (node (ref "C68") (pin "1") (pintype "passive"))
      (node (ref "FB2") (pin "1") (pintype "passive"))
      (node (ref "R9") (pin "2") (pintype "passive"))
      (node (ref "U1") (pin "L3") (pinfunction "VDDA_L3") (pintype "passive"))
    )
    (net (code "212") (name "Net-(U1L-VLXSMPS)") (class "Default")
      (node (ref "C76") (pin "2") (pintype "passive"))
      (node (ref "L5") (pin "1") (pintype "passive"))
      (node (ref "U1") (pin "R12") (pinfunction "VLXSMPS_R12") (pintype "passive"))
    )
    (net (code "213") (name "VBAT") (class "Default")
      (node (ref "C7") (pin "1") (pintype "passive"))
      (node (ref "U1") (pin "D3") (pinfunction "VBAT_D3") (pintype "passive"))
    )
    (net (code "214") (name "unconnected-(J1-NC-Pad1)") (class "Default")
      (node (ref "J1") (pin "1") (pinfunction "NC_1") (pintype "passive"))
    )
    (net (code "215") (name "unconnected-(J1-NC-Pad2)") (class "Default")
      (node (ref "J1") (pin "2") (pinfunction "NC_2") (pintype "passive"))
    )
    (net (code "216") (name "unconnected-(J1-T_JRCLK{slash}NC-Pad9)") (class "Default")
      (node (ref "J1") (pin "9") (pinfunction "T_JRCLK/NC_9") (pintype "passive"))
    )
    (net (code "217") (name "unconnected-(J1-T_JTDI{slash}NC-Pad10)") (class "Default")
      (node (ref "J1") (pin "10") (pinfunction "T_JTDI/NC_10") (pintype "passive"))
    )
    (net (code "218") (name "unconnected-(U1A-JTDI_{slash}_PA15-PadC13)") (class "Default")
      (node (ref "U1") (pin "C13") (pinfunction "JTDI_/_PA15_C13") (pintype "passive"))
    )
    (net (code "219") (name "unconnected-(U1A-PA9-PadG13)") (class "Default")
      (node (ref "U1") (pin "G13") (pinfunction "PA9_G13") (pintype "passive"))
    )
    (net (code "220") (name "unconnected-(U1A-PA10-PadF13)") (class "Default")
      (node (ref "U1") (pin "F13") (pinfunction "PA10_F13") (pintype "passive"))
    )
    (net (code "221") (name "unconnected-(U1B-PB1-PadL6)") (class "Default")
      (node (ref "U1") (pin "L6") (pinfunction "PB1_L6") (pintype "passive"))
    )
    (net (code "222") (name "unconnected-(U1B-PB2-PadP4)") (class "Default")
      (node (ref "U1") (pin "P4") (pinfunction "PB2_P4") (pintype "passive"))
    )
    (net (code "223") (name "unconnected-(U1B-PB5-PadE7)") (class "Default")
      (node (ref "U1") (pin "E7") (pinfunction "PB5_E7") (pintype "passive"))
    )
    (net (code "224") (name "unconnected-(U1B-PB14-PadK11)") (class "Default")
      (node (ref "U1") (pin "K11") (pinfunction "PB14_K11") (pintype "passive"))
    )
    (net (code "225") (name "unconnected-(U1B-nJTRST_{slash}_PB4-PadC7)") (class "Default")
      (node (ref "U1") (pin "C7") (pinfunction "nJTRST_/_PB4_C7") (pintype "passive"))
    )
    (net (code "226") (name "unconnected-(U1C-PC0-PadL1)") (class "Default")
      (node (ref "U1") (pin "L1") (pinfunction "PC0_L1") (pintype "passive"))
    )
    (net (code "227") (name "unconnected-(U1C-PC2-PadM1)") (class "Default")
      (node (ref "U1") (pin "M1") (pinfunction "PC2_M1") (pintype "passive"))
    )
    (net (code "228") (name "unconnected-(U1C-PC13-PadC3)") (class "Default")
      (node (ref "U1") (pin "C3") (pinfunction "PC13_C3") (pintype "passive"))
    )
    (net (code "229") (name "unconnected-(U1D-PD0-PadE10)") (class "Default")
      (node (ref "U1") (pin "E10") (pinfunction "PD0_E10") (pintype "passive"))
    )
    (net (code "230") (name "unconnected-(U1D-PD1-PadC12)") (class "Default")
      (node (ref "U1") (pin "C12") (pinfunction "PD1_C12") (pintype "passive"))
    )
    (net (code "231") (name "unconnected-(U1D-PD7-PadC9)") (class "Default")
      (node (ref "U1") (pin "C9") (pinfunction "PD7_C9") (pintype "passive"))
    )
    (net (code "232") (name "unconnected-(U1D-PD8-PadL12)") (class "Default")
      (node (ref "U1") (pin "L12") (pinfunction "PD8_L12") (pintype "passive"))
    )
    (net (code "233") (name "unconnected-(U1D-PD10-PadN14)") (class "Default")
      (node (ref "U1") (pin "N14") (pinfunction "PD10_N14") (pintype "passive"))
    )
    (net (code "234") (name "unconnected-(U1D-PD11-PadN15)") (class "Default")
      (node (ref "U1") (pin "N15") (pinfunction "PD11_N15") (pintype "passive"))
    )
    (net (code "235") (name "unconnected-(U1D-PD15-PadK12)") (class "Default")
      (node (ref "U1") (pin "K12") (pinfunction "PD15_K12") (pintype "passive"))
    )
    (net (code "236") (name "unconnected-(U1E-PE9-PadN8)") (class "Default")
      (node (ref "U1") (pin "N8") (pinfunction "PE9_N8") (pintype "passive"))
    )
    (net (code "237") (name "unconnected-(U1F-PF0-PadE1)") (class "Default")
      (node (ref "U1") (pin "E1") (pinfunction "PF0_E1") (pintype "passive"))
    )
    (net (code "238") (name "unconnected-(U1F-PF1-PadG4)") (class "Default")
      (node (ref "U1") (pin "G4") (pinfunction "PF1_G4") (pintype "passive"))
    )
    (net (code "239") (name "unconnected-(U1F-PF2-PadF2)") (class "Default")
      (node (ref "U1") (pin "F2") (pinfunction "PF2_F2") (pintype "passive"))
    )
    (net (code "240") (name "unconnected-(U1F-PF3-PadH5)") (class "Default")
      (node (ref "U1") (pin "H5") (pinfunction "PF3_H5") (pintype "passive"))
    )
    (net (code "241") (name "unconnected-(U1F-PF4-PadG1)") (class "Default")
      (node (ref "U1") (pin "G1") (pinfunction "PF4_G1") (pintype "passive"))
    )
    (net (code "242") (name "unconnected-(U1F-PF5-PadH4)") (class "Default")
      (node (ref "U1") (pin "H4") (pinfunction "PF5_H4") (pintype "passive"))
    )
    (net (code "243") (name "unconnected-(U1F-PF10-PadK1)") (class "Default")
      (node (ref "U1") (pin "K1") (pinfunction "PF10_K1") (pintype "passive"))
    )
    (net (code "244") (name "unconnected-(U1F-PF11-PadL7)") (class "Default")
      (node (ref "U1") (pin "L7") (pinfunction "PF11_L7") (pintype "passive"))
    )
    (net (code "245") (name "unconnected-(U1F-PF12-PadP6)") (class "Default")
      (node (ref "U1") (pin "P6") (pinfunction "PF12_P6") (pintype "passive"))
    )
    (net (code "246") (name "unconnected-(U1G-PG0-PadP7)") (class "Default")
      (node (ref "U1") (pin "P7") (pinfunction "PG0_P7") (pintype "passive"))
    )
    (net (code "247") (name "unconnected-(U1G-PG1-PadR7)") (class "Default")
      (node (ref "U1") (pin "R7") (pinfunction "PG1_R7") (pintype "passive"))
    )
    (net (code "248") (name "unconnected-(U1G-PG6-PadJ13)") (class "Default")
      (node (ref "U1") (pin "J13") (pinfunction "PG6_J13") (pintype "passive"))
    )
    (net (code "249") (name "unconnected-(U1G-PG7-PadH11)") (class "Default")
      (node (ref "U1") (pin "H11") (pinfunction "PG7_H11") (pintype "passive"))
    )
    (net (code "250") (name "unconnected-(U1G-PG9-PadB9)") (class "Default")
      (node (ref "U1") (pin "B9") (pinfunction "PG9_B9") (pintype "passive"))
    )
    (net (code "251") (name "unconnected-(U1G-PG10-PadA9)") (class "Default")
      (node (ref "U1") (pin "A9") (pinfunction "PG10_A9") (pintype "passive"))
    )
    (net (code "252") (name "unconnected-(U1G-PG15-PadA7)") (class "Default")
      (node (ref "U1") (pin "A7") (pinfunction "PG15_A7") (pintype "passive"))
    )
    (net (code "253") (name "unconnected-(U1H-PH4-PadP1)") (class "Default")
      (node (ref "U1") (pin "P1") (pinfunction "PH4_P1") (pintype "passive"))
    )
    (net (code "254") (name "unconnected-(U1H-PH5-PadK6)") (class "Default")
      (node (ref "U1") (pin "K6") (pinfunction "PH5_K6") (pintype "passive"))
    )
    (net (code "255") (name "unconnected-(U1H-PH7-PadM11)") (class "Default")
      (node (ref "U1") (pin "M11") (pinfunction "PH7_M11") (pintype "passive"))
    )
    (net (code "256") (name "unconnected-(U1H-PH8-PadN12)") (class "Default")
      (node (ref "U1") (pin "N12") (pinfunction "PH8_N12") (pintype "passive"))
    )
    (net (code "257") (name "unconnected-(U1H-PH10-PadK10)") (class "Default")
      (node (ref "U1") (pin "K10") (pinfunction "PH10_K10") (pintype "passive"))
    )
    (net (code "258") (name "unconnected-(U1H-PH11-PadM12)") (class "Default")
      (node (ref "U1") (pin "M12") (pinfunction "PH11_M12") (pintype "passive"))
    )
    (net (code "259") (name "unconnected-(U1H-PH12-PadR14)") (class "Default")
      (node (ref "U1") (pin "R14") (pinfunction "PH12_R14") (pintype "passive"))
    )
    (net (code "260") (name "unconnected-(U1I-PI0-PadE12)") (class "Default")
      (node (ref "U1") (pin "E12") (pinfunction "PI0_E12") (pintype "passive"))
    )
    (net (code "261") (name "unconnected-(U1I-PI4-PadC5)") (class "Default")
      (node (ref "U1") (pin "C5") (pinfunction "PI4_C5") (pintype "passive"))
    )
    (net (code "262") (name "unconnected-(U1I-PI10-PadC1)") (class "Default")
      (node (ref "U1") (pin "C1") (pinfunction "PI10_C1") (pintype "passive"))
    )
    (net (code "263") (name "unconnected-(U1I-PI12-PadF1)") (class "Default")
      (node (ref "U1") (pin "F1") (pinfunction "PI12_F1") (pintype "passive"))
    )
    (net (code "264") (name "unconnected-(U1I-PI13-PadG3)") (class "Default")
      (node (ref "U1") (pin "G3") (pinfunction "PI13_G3") (pintype "passive"))
    )
    (net (code "265") (name "unconnected-(U1I-PI14-PadG2)") (class "Default")
      (node (ref "U1") (pin "G2") (pinfunction "PI14_G2") (pintype "passive"))
    )
    (net (code "266") (name "unconnected-(U1I-PI15-PadN5)") (class "Default")
      (node (ref "U1") (pin "N5") (pinfunction "PI15_N5") (pintype "passive"))
    )
    (net (code "267") (name "unconnected-(U1J-PJ10-PadD13)") (class "Default")
      (node (ref "U1") (pin "D13") (pinfunction "PJ10_D13") (pintype "passive"))
    )
    (net (code "268") (name "unconnected-(U1J-PJ11-PadC14)") (class "Default")
      (node (ref "U1") (pin "C14") (pinfunction "PJ11_C14") (pintype "passive"))
    )
    (net (code "269") (name "unconnected-(U1J-PJ12-PadA13)") (class "Default")
      (node (ref "U1") (pin "A13") (pinfunction "PJ12_A13") (pintype "passive"))
    )
    (net (code "270") (name "unconnected-(U1K-PK0-PadM15)") (class "Default")
      (node (ref "U1") (pin "M15") (pinfunction "PK0_M15") (pintype "passive"))
    )
    (net (code "271") (name "unconnected-(U1K-PK1-PadL14)") (class "Default")
      (node (ref "U1") (pin "L14") (pinfunction "PK1_L14") (pintype "passive"))
    )
    (net (code "272") (name "unconnected-(U1K-PK2-PadK13)") (class "Default")
      (node (ref "U1") (pin "K13") (pinfunction "PK2_K13") (pintype "passive"))
    )
    (net (code "273") (name "unconnected-(U1K-PK3-PadA12)") (class "Default")
      (node (ref "U1") (pin "A12") (pinfunction "PK3_A12") (pintype "passive"))
    )
    (net (code "274") (name "unconnected-(U1K-PK4-PadB11)") (class "Default")
      (node (ref "U1") (pin "B11") (pinfunction "PK4_B11") (pintype "passive"))
    )
    (net (code "275") (name "unconnected-(U1K-PK12-PadF5)") (class "Default")
      (node (ref "U1") (pin "F5") (pinfunction "PK12_F5") (pintype "passive"))
    )
    (net (code "276") (name "unconnected-(U1K-PK13-PadB1)") (class "Default")
      (node (ref "U1") (pin "B1") (pinfunction "PK13_B1") (pintype "passive"))
    )
    (net (code "277") (name "unconnected-(U1K-PK14-PadF4)") (class "Default")
      (node (ref "U1") (pin "F4") (pinfunction "PK14_F4") (pintype "passive"))
    )
    (net (code "278") (name "unconnected-(U1K-PK15-PadG5)") (class "Default")
      (node (ref "U1") (pin "G5") (pinfunction "PK15_G5") (pintype "passive"))
    )
    (net (code "279") (name "unconnected-(U1M-OTG_HS_DM-PadH15)") (class "Default")
      (node (ref "U1") (pin "H15") (pinfunction "OTG_HS_DM_H15") (pintype "passive"))
    )
    (net (code "280") (name "unconnected-(U1M-OTG_HS_DP-PadG15)") (class "Default")
      (node (ref "U1") (pin "G15") (pinfunction "OTG_HS_DP_G15") (pintype "passive"))
    )
  )
)
